# ElectroLab_R2.net
KiCad netlist of a schematic drawn in EAGLE
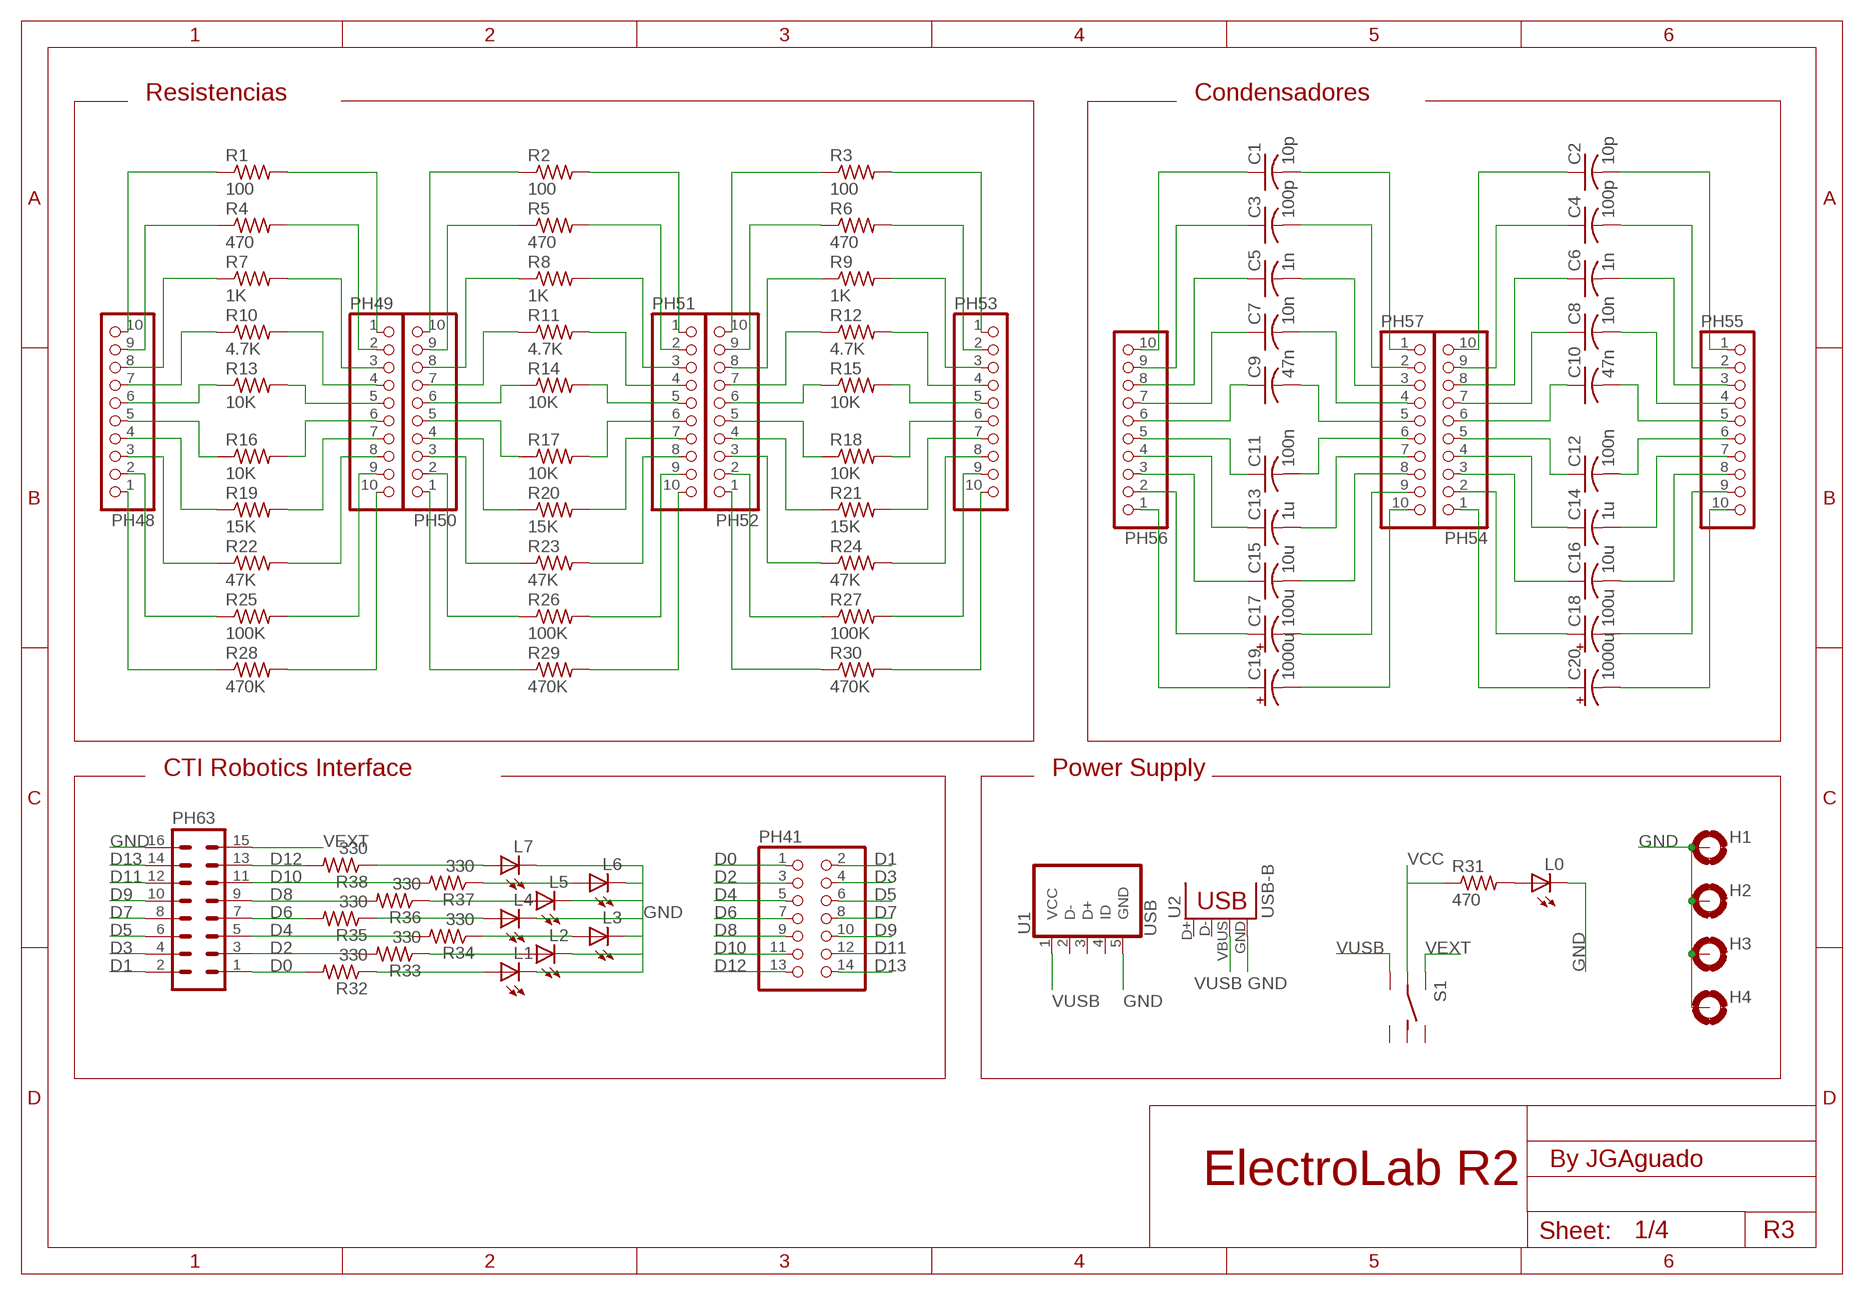
[diagram p0: schematic, sheet 1]
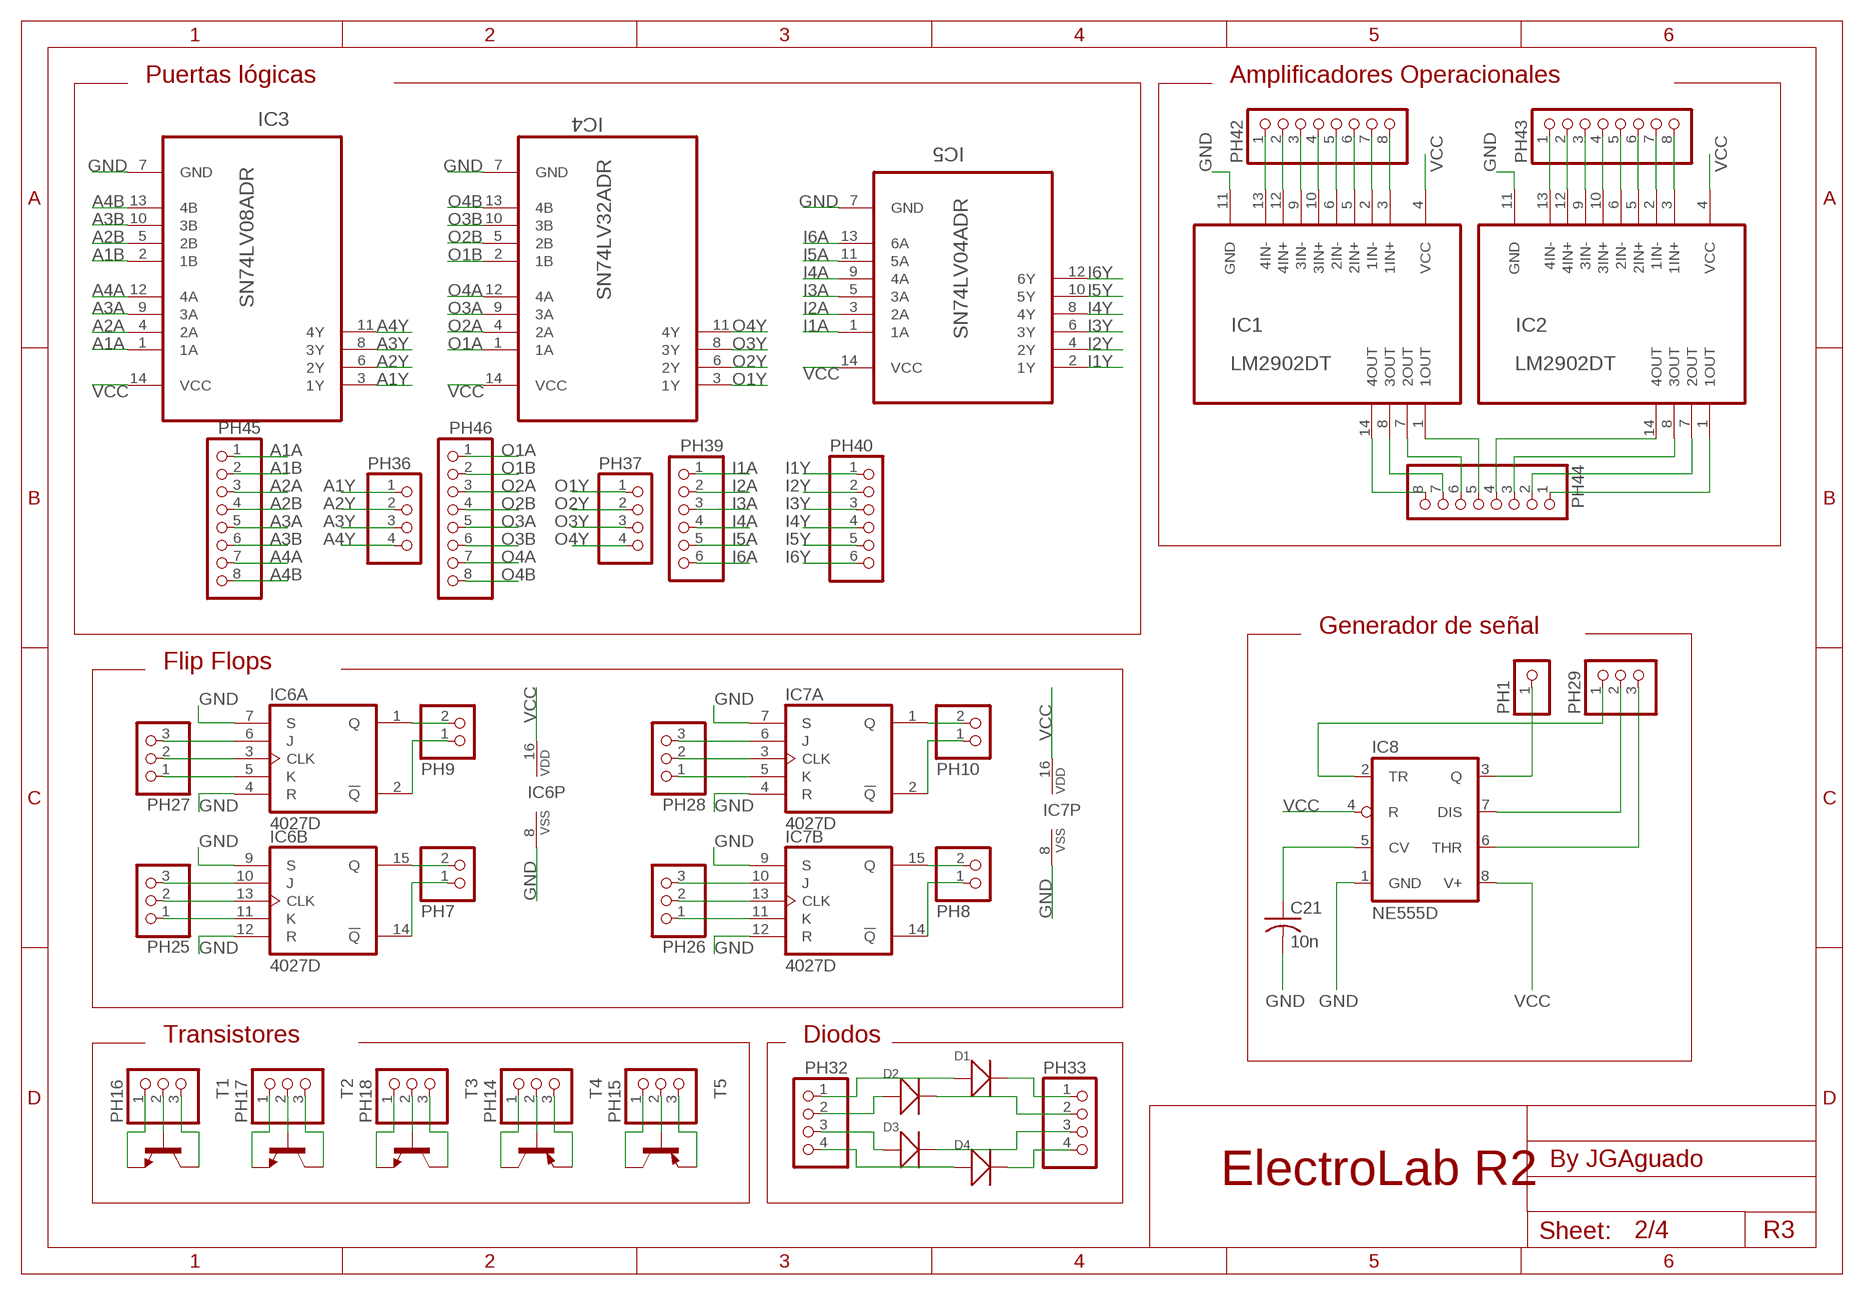
[diagram p1: schematic, sheet 2]
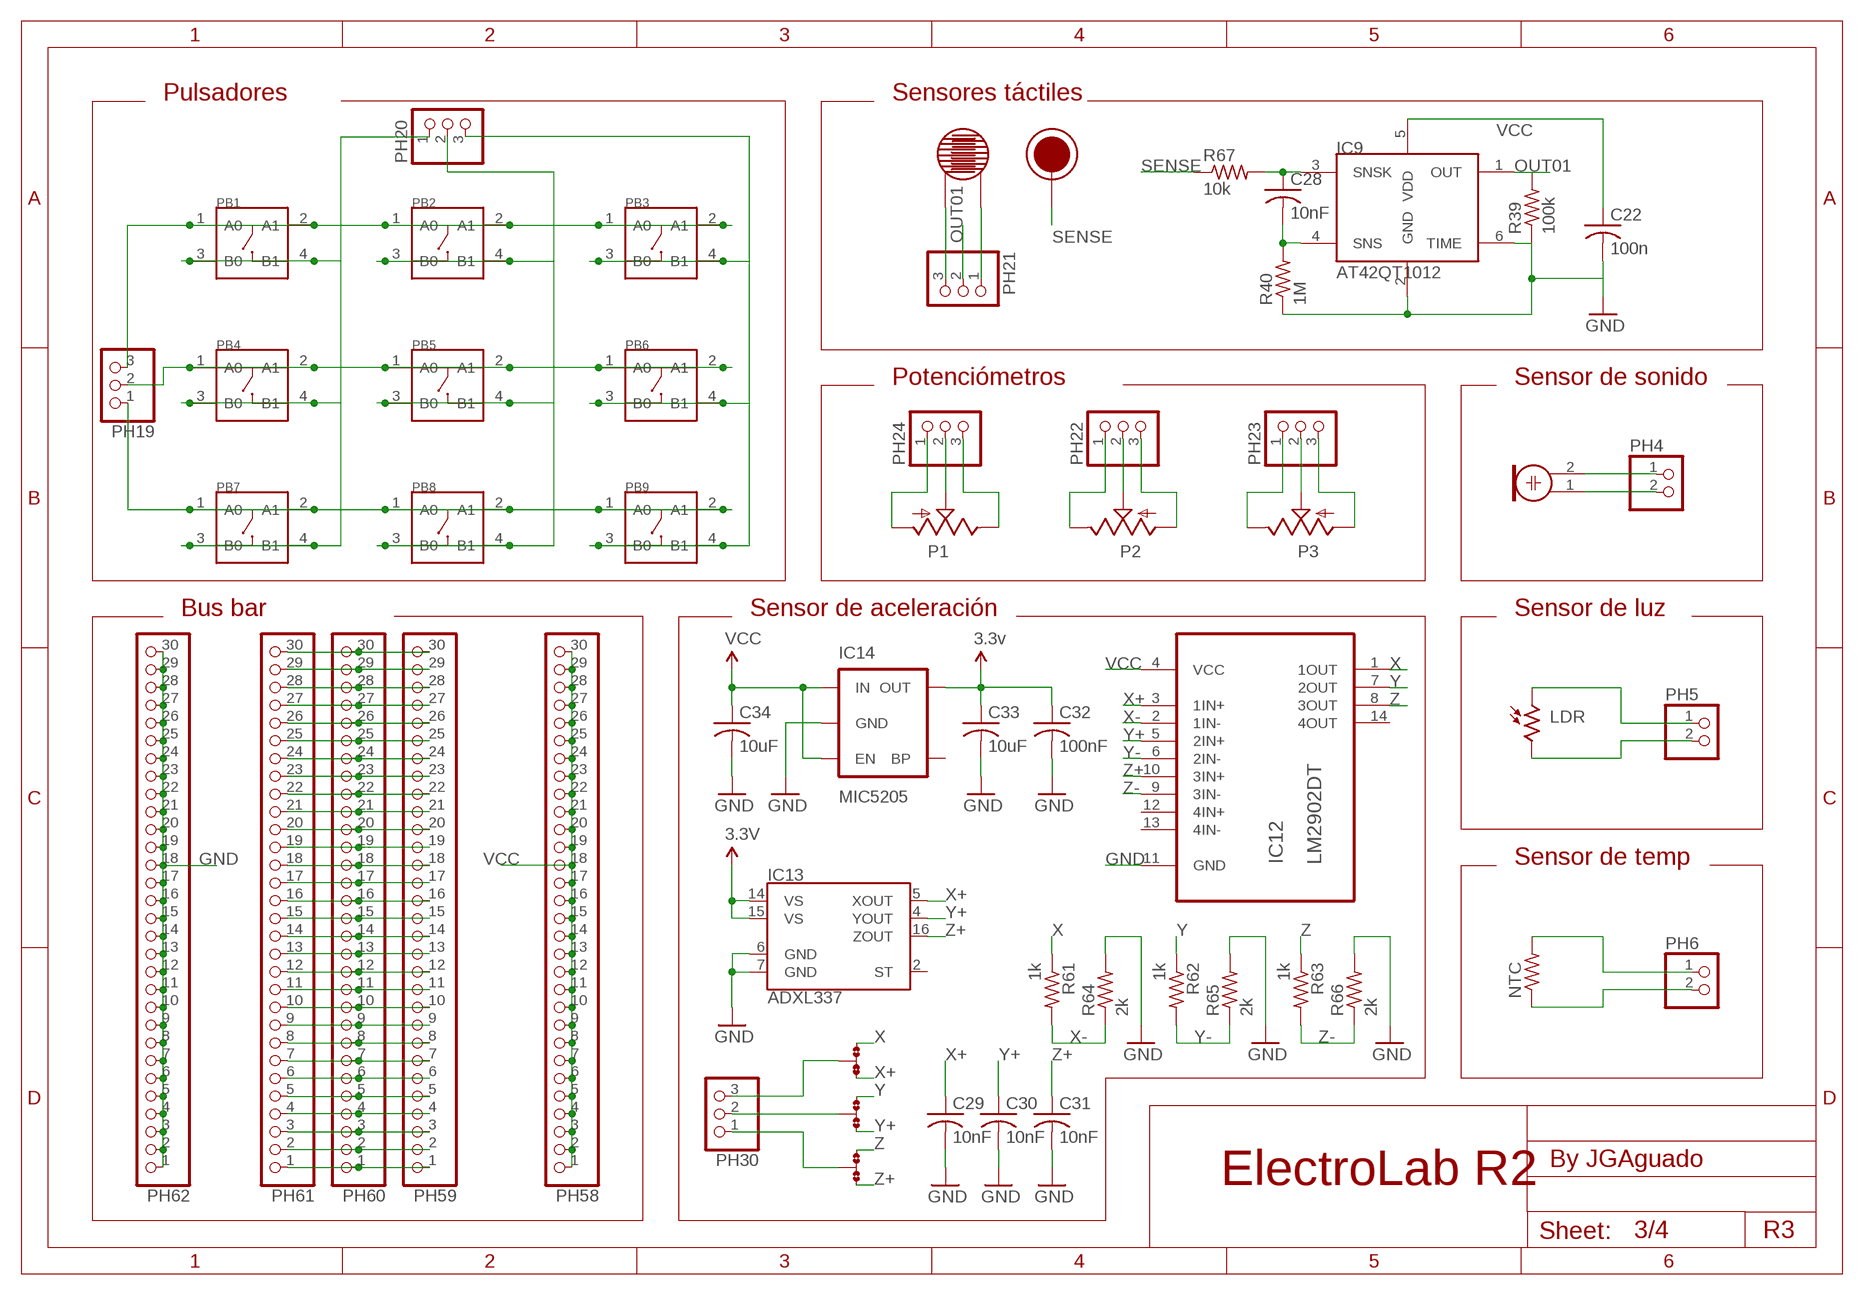
[diagram p2: schematic, sheet 3]
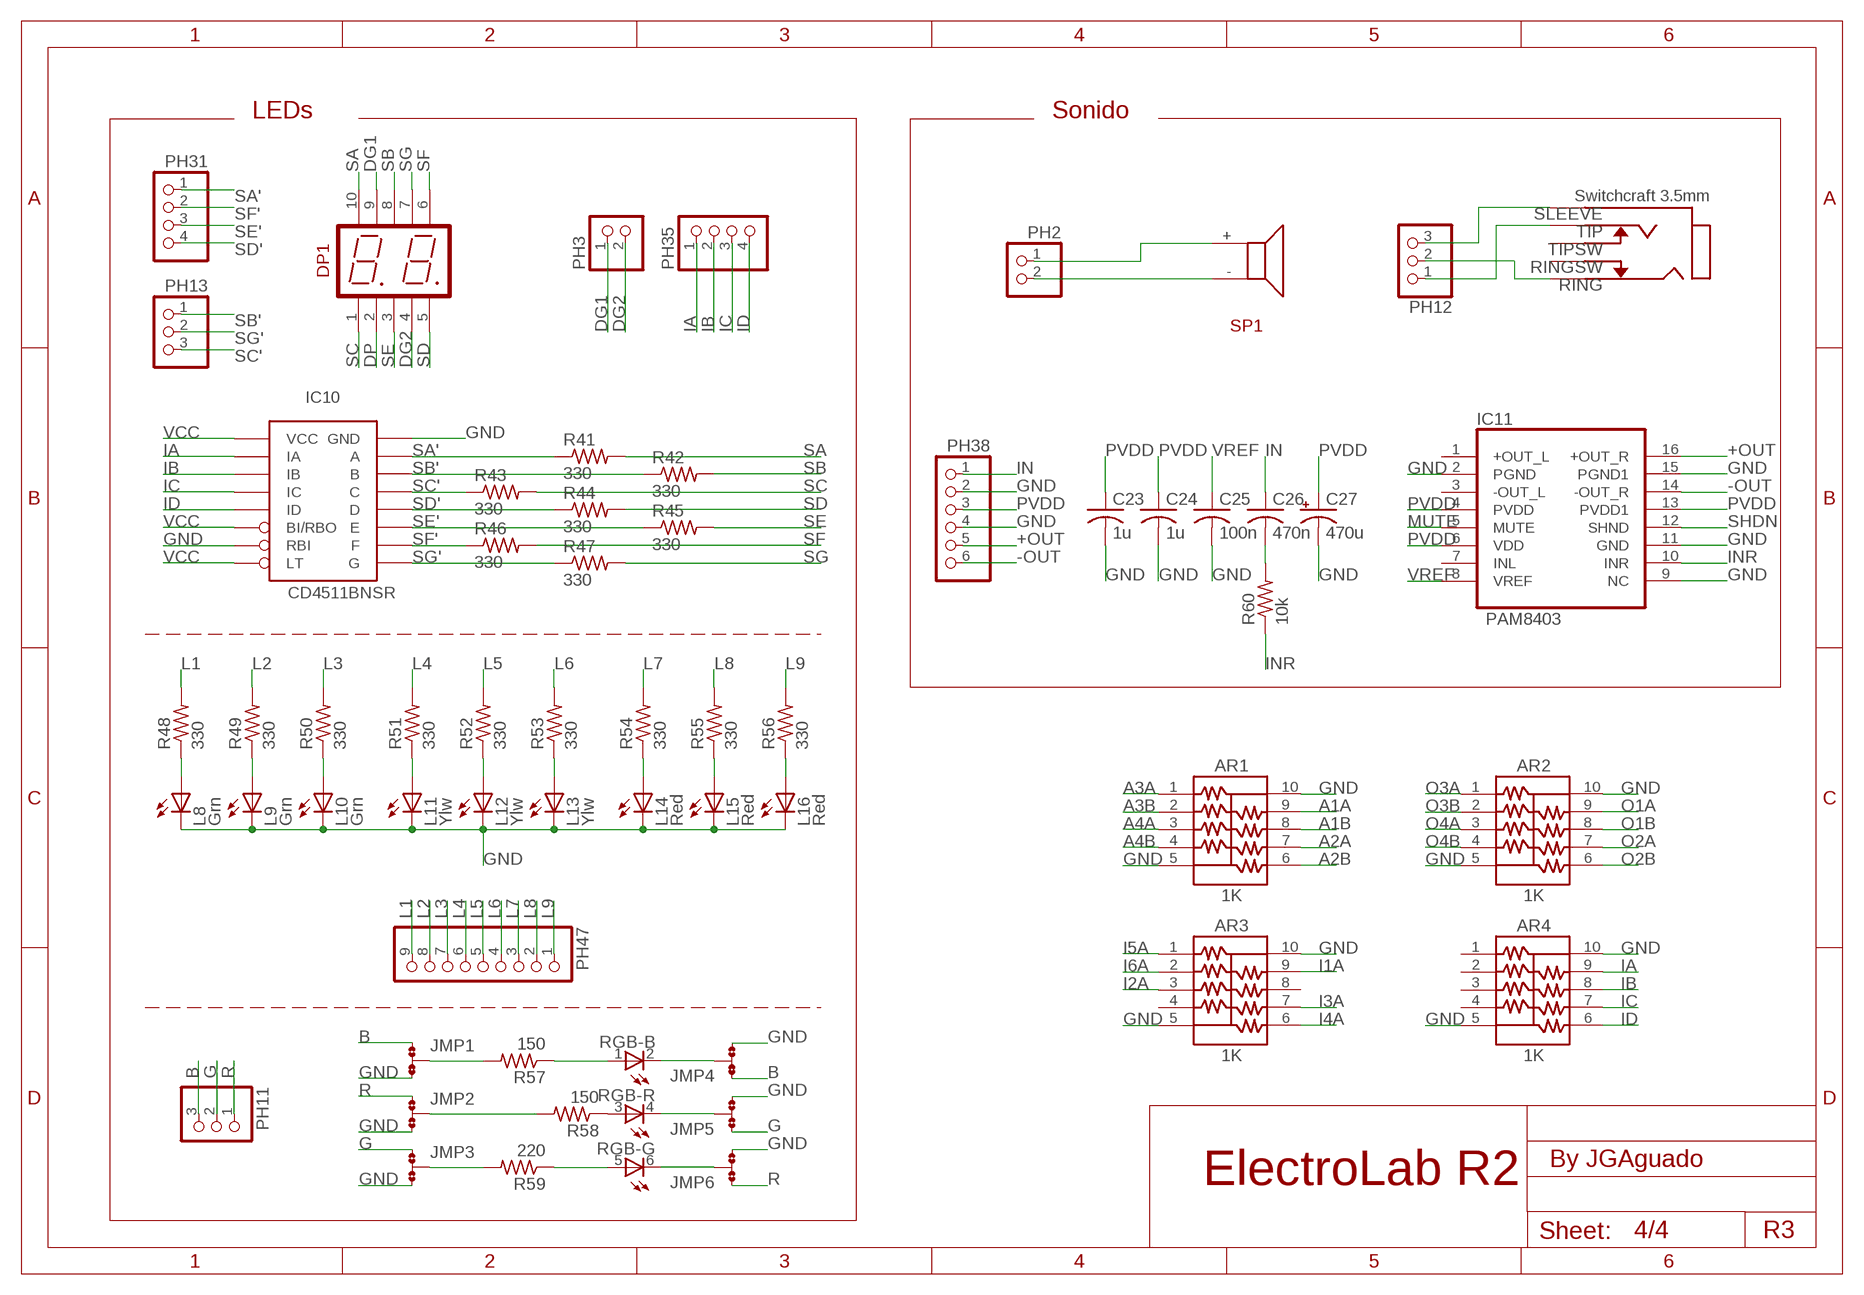
[diagram p3: schematic, sheet 4]

(export (version "E")
  (design (tool "Eeschema 10.0.6"))
  (components
    (comp (ref "C21")
      (value "10n")
      (footprint "eagle-import:C1206")
      (libsource (lib "eagle-import") (part "C-USC1206"))
    )
    (comp (ref "D1")
      (value "SMD-DIODE-SWITCHING-75V-150MA(D1206)")
      (footprint "eagle-import:LED-1206")
      (fields (field (name "MPN") "CD1206-S01575"))
      (libsource (lib "eagle-import") (part "SMD-DIODE-SWITCHING-75V-150MA(D1206)"))
    )
    (comp (ref "D2")
      (value "SMD-DIODE-SWITCHING-75V-150MA(D1206)")
      (footprint "eagle-import:LED-1206")
      (fields (field (name "MPN") "CD1206-S01575"))
      (libsource (lib "eagle-import") (part "SMD-DIODE-SWITCHING-75V-150MA(D1206)"))
    )
    (comp (ref "D3")
      (value "SMD-DIODE-SWITCHING-75V-150MA(D1206)")
      (footprint "eagle-import:LED-1206")
      (fields (field (name "MPN") "CD1206-S01575"))
      (libsource (lib "eagle-import") (part "SMD-DIODE-SWITCHING-75V-150MA(D1206)"))
    )
    (comp (ref "D4")
      (value "SMD-DIODE-SWITCHING-75V-150MA(D1206)")
      (footprint "eagle-import:LED-1206")
      (fields (field (name "MPN") "CD1206-S01575"))
      (libsource (lib "eagle-import") (part "SMD-DIODE-SWITCHING-75V-150MA(D1206)"))
    )
    (comp (ref "IC1")
      (value "LM2902DT")
      (footprint "eagle-import:SOIC127P600X175-14N")
      (libsource (lib "eagle-import") (part "LM2902DT"))
    )
    (comp (ref "IC2")
      (value "LM2902DT")
      (footprint "eagle-import:SOIC127P600X175-14N")
      (libsource (lib "eagle-import") (part "LM2902DT"))
    )
    (comp (ref "IC3")
      (value "SN74LV08ADR")
      (footprint "eagle-import:SOIC127P600X175-14N")
      (fields (field (name "MPN") "SN74LVC08AD"))
      (libsource (lib "eagle-import") (part "SN74LVC08AD"))
    )
    (comp (ref "IC4")
      (value "SN74LV32ADR")
      (footprint "eagle-import:SOIC127P600X175-14N")
      (fields (field (name "MPN") "SN74S32D"))
      (libsource (lib "eagle-import") (part "SN74S32D"))
    )
    (comp (ref "IC5")
      (value "SN74LV04ADR")
      (footprint "eagle-import:SOIC127P600X175-14N")
      (libsource (lib "eagle-import") (part "SN74LV04ADR"))
    )
    (comp (ref "IC6")
      (value "4027D")
      (footprint "eagle-import:SO16")
      (libsource (lib "eagle-import") (part "4027D"))
    )
    (comp (ref "IC7")
      (value "4027D")
      (footprint "eagle-import:SO16")
      (libsource (lib "eagle-import") (part "4027D"))
    )
    (comp (ref "IC8")
      (value "NE555D")
      (footprint "eagle-import:SO08")
      (libsource (lib "eagle-import") (part "555DNE"))
    )
    (comp (ref "PH1")
      (value "PINHD-1X1")
      (footprint "eagle-import:1X01")
      (libsource (lib "eagle-import") (part "PINHD-1X1"))
    )
    (comp (ref "PH7")
      (value "PINHD-1X2")
      (footprint "eagle-import:1X02")
      (libsource (lib "eagle-import") (part "PINHD-1X2"))
    )
    (comp (ref "PH8")
      (value "PINHD-1X2")
      (footprint "eagle-import:1X02")
      (libsource (lib "eagle-import") (part "PINHD-1X2"))
    )
    (comp (ref "PH9")
      (value "PINHD-1X2")
      (footprint "eagle-import:1X02")
      (libsource (lib "eagle-import") (part "PINHD-1X2"))
    )
    (comp (ref "PH10")
      (value "PINHD-1X2")
      (footprint "eagle-import:1X02")
      (libsource (lib "eagle-import") (part "PINHD-1X2"))
    )
    (comp (ref "PH14")
      (value "PINHD-1X3")
      (footprint "eagle-import:1X03")
      (libsource (lib "eagle-import") (part "PINHD-1X3"))
    )
    (comp (ref "PH15")
      (value "PINHD-1X3")
      (footprint "eagle-import:1X03")
      (libsource (lib "eagle-import") (part "PINHD-1X3"))
    )
    (comp (ref "PH16")
      (value "PINHD-1X3")
      (footprint "eagle-import:1X03")
      (libsource (lib "eagle-import") (part "PINHD-1X3"))
    )
    (comp (ref "PH17")
      (value "PINHD-1X3")
      (footprint "eagle-import:1X03")
      (libsource (lib "eagle-import") (part "PINHD-1X3"))
    )
    (comp (ref "PH18")
      (value "PINHD-1X3")
      (footprint "eagle-import:1X03")
      (libsource (lib "eagle-import") (part "PINHD-1X3"))
    )
    (comp (ref "PH25")
      (value "PINHD-1X3")
      (footprint "eagle-import:1X03")
      (libsource (lib "eagle-import") (part "PINHD-1X3"))
    )
    (comp (ref "PH26")
      (value "PINHD-1X3")
      (footprint "eagle-import:1X03")
      (libsource (lib "eagle-import") (part "PINHD-1X3"))
    )
    (comp (ref "PH27")
      (value "PINHD-1X3")
      (footprint "eagle-import:1X03")
      (libsource (lib "eagle-import") (part "PINHD-1X3"))
    )
    (comp (ref "PH28")
      (value "PINHD-1X3")
      (footprint "eagle-import:1X03")
      (libsource (lib "eagle-import") (part "PINHD-1X3"))
    )
    (comp (ref "PH29")
      (value "PINHD-1X3")
      (footprint "eagle-import:1X03")
      (libsource (lib "eagle-import") (part "PINHD-1X3"))
    )
    (comp (ref "PH32")
      (value "PINHD-1X4")
      (footprint "eagle-import:1X04")
      (libsource (lib "eagle-import") (part "PINHD-1X4"))
    )
    (comp (ref "PH33")
      (value "PINHD-1X4")
      (footprint "eagle-import:1X04")
      (libsource (lib "eagle-import") (part "PINHD-1X4"))
    )
    (comp (ref "PH36")
      (value "PINHD-1X4")
      (footprint "eagle-import:1X04")
      (libsource (lib "eagle-import") (part "PINHD-1X4"))
    )
    (comp (ref "PH37")
      (value "PINHD-1X4")
      (footprint "eagle-import:1X04")
      (libsource (lib "eagle-import") (part "PINHD-1X4"))
    )
    (comp (ref "PH39")
      (value "PINHD-1X6")
      (footprint "eagle-import:1X06")
      (libsource (lib "eagle-import") (part "PINHD-1X6"))
    )
    (comp (ref "PH40")
      (value "PINHD-1X6")
      (footprint "eagle-import:1X06")
      (libsource (lib "eagle-import") (part "PINHD-1X6"))
    )
    (comp (ref "PH42")
      (value "PINHD-1X8")
      (footprint "eagle-import:1X08")
      (libsource (lib "eagle-import") (part "PINHD-1X8"))
    )
    (comp (ref "PH43")
      (value "PINHD-1X8")
      (footprint "eagle-import:1X08")
      (libsource (lib "eagle-import") (part "PINHD-1X8"))
    )
    (comp (ref "PH44")
      (value "PINHD-1X8")
      (footprint "eagle-import:1X08")
      (libsource (lib "eagle-import") (part "PINHD-1X8"))
    )
    (comp (ref "PH45")
      (value "PINHD-1X8")
      (footprint "eagle-import:1X08")
      (libsource (lib "eagle-import") (part "PINHD-1X8"))
    )
    (comp (ref "PH46")
      (value "PINHD-1X8")
      (footprint "eagle-import:1X08")
      (libsource (lib "eagle-import") (part "PINHD-1X8"))
    )
    (comp (ref "T1")
      (value "BC817-16-NPN-SOT23-BEC")
      (footprint "eagle-import:SOT23-BEC")
      (libsource (lib "eagle-import") (part "-NPN-SOT23-BECBC817-16"))
    )
    (comp (ref "T2")
      (value "BC817-16-NPN-SOT23-BEC")
      (footprint "eagle-import:SOT23-BEC")
      (libsource (lib "eagle-import") (part "-NPN-SOT23-BECBC817-16"))
    )
    (comp (ref "T3")
      (value "BC817-16-NPN-SOT23-BEC")
      (footprint "eagle-import:SOT23-BEC")
      (libsource (lib "eagle-import") (part "-NPN-SOT23-BECBC817-16"))
    )
    (comp (ref "T4")
      (value "-PNP-SOT23-BCE")
      (footprint "eagle-import:SOT23-BCE")
      (libsource (lib "eagle-import") (part "-PNP-SOT23-BCE"))
    )
    (comp (ref "T5")
      (value "-PNP-SOT23-BCE")
      (footprint "eagle-import:SOT23-BCE")
      (libsource (lib "eagle-import") (part "-PNP-SOT23-BCE"))
    )
    (comp (ref "C22")
      (value "100n")
      (footprint "eagle-import:0603")
      (libsource (lib "eagle-import") (part "C0603"))
    )
    (comp (ref "C28")
      (value "10nF")
      (footprint "eagle-import:0603")
      (libsource (lib "eagle-import") (part "C0603"))
    )
    (comp (ref "C29")
      (value "10nF")
      (footprint "eagle-import:0603")
      (libsource (lib "eagle-import") (part "C0603"))
    )
    (comp (ref "C30")
      (value "10nF")
      (footprint "eagle-import:0603")
      (libsource (lib "eagle-import") (part "C0603"))
    )
    (comp (ref "C31")
      (value "10nF")
      (footprint "eagle-import:0603")
      (libsource (lib "eagle-import") (part "C0603"))
    )
    (comp (ref "C32")
      (value "100nF")
      (footprint "eagle-import:0603")
      (libsource (lib "eagle-import") (part "C0603"))
    )
    (comp (ref "C33")
      (value "10uF")
      (footprint "eagle-import:0603")
      (libsource (lib "eagle-import") (part "C0603"))
    )
    (comp (ref "C34")
      (value "10uF")
      (footprint "eagle-import:0603")
      (libsource (lib "eagle-import") (part "C0603"))
    )
    (comp (ref "IC9")
      (value "AT42QT1012")
      (footprint "eagle-import:SOT-23-6")
      (libsource (lib "eagle-import") (part "AT42QT1012"))
    )
    (comp (ref "IC12")
      (value "LM2902DT")
      (footprint "eagle-import:SOIC127P600X175-14N")
      (libsource (lib "eagle-import") (part "LM2902DT"))
    )
    (comp (ref "IC13")
      (value "ADXL337")
      (footprint "eagle-import:LFCSP-3X3")
      (libsource (lib "eagle-import") (part "ADXL337"))
    )
    (comp (ref "IC14")
      (value "MIC5205")
      (footprint "eagle-import:SOT23-5")
      (libsource (lib "eagle-import") (part "V_REG_LDOSMD"))
    )
    (comp (ref "JMP7")
      (value "0R-JUMPA")
      (footprint "eagle-import:A0R-JMP")
      (libsource (lib "eagle-import") (part "jump-0r-smd_251_0R-JUMPA"))
    )
    (comp (ref "JMP8")
      (value "0R-JUMPA")
      (footprint "eagle-import:A0R-JMP")
      (libsource (lib "eagle-import") (part "jump-0r-smd_251_0R-JUMPA"))
    )
    (comp (ref "JMP9")
      (value "0R-JUMPA")
      (footprint "eagle-import:A0R-JMP")
      (libsource (lib "eagle-import") (part "jump-0r-smd_251_0R-JUMPA"))
    )
    (comp (ref "LDR")
      (value "V1060_21")
      (footprint "eagle-import:TO-5_V10")
      (libsource (lib "eagle-import") (part "?1060V_21"))
    )
    (comp (ref "MIC")
      (value "ELECTRET_MICROPHON-WM-64PC/64PK")
      (footprint "eagle-import:WM-64PC_64PK")
      (libsource (lib "eagle-import") (part "ELECTRET_MICROPHON-WM-64PC/64PK"))
    )
    (comp (ref "NTC")
      (value "R-US_R1206")
      (footprint "eagle-import:R1206")
      (libsource (lib "eagle-import") (part "R-US_R1206"))
    )
    (comp (ref "P1")
      (value "SLIDE_POT_20MM")
      (footprint "eagle-import:SLIDE_POT_20MM")
      (libsource (lib "eagle-import") (part "SLIDE_POT_20MM"))
    )
    (comp (ref "P2")
      (value "ALPS_RK09K_VERTICAL")
      (footprint "eagle-import:ALPS_RK09K_VERTICAL")
      (libsource (lib "eagle-import") (part "ALPS_RK09K_VERTICAL"))
    )
    (comp (ref "P3")
      (value "ALPS_RK09K_VERTICAL")
      (footprint "eagle-import:ALPS_RK09K_VERTICAL")
      (libsource (lib "eagle-import") (part "ALPS_RK09K_VERTICAL"))
    )
    (comp (ref "PB1")
      (value "SMD-SWITCH-TACTILE-SPST-NO/TS-1109(4P-D6.0MM)")
      (footprint "eagle-import:SW4-SMD-6.0X6.0X5.0MM")
      (fields (field (name "MPN") "TS-1109"))
      (libsource (lib "eagle-import") (part "SMD-SWITCH-TACTILE-SPST-NO/TS-1109(4P-D6.0MM)"))
    )
    (comp (ref "PB2")
      (value "SMD-SWITCH-TACTILE-SPST-NO/TS-1109(4P-D6.0MM)")
      (footprint "eagle-import:SW4-SMD-6.0X6.0X5.0MM")
      (fields (field (name "MPN") "TS-1109"))
      (libsource (lib "eagle-import") (part "SMD-SWITCH-TACTILE-SPST-NO/TS-1109(4P-D6.0MM)"))
    )
    (comp (ref "PB3")
      (value "SMD-SWITCH-TACTILE-SPST-NO/TS-1109(4P-D6.0MM)")
      (footprint "eagle-import:SW4-SMD-6.0X6.0X5.0MM")
      (fields (field (name "MPN") "TS-1109"))
      (libsource (lib "eagle-import") (part "SMD-SWITCH-TACTILE-SPST-NO/TS-1109(4P-D6.0MM)"))
    )
    (comp (ref "PB4")
      (value "SMD-SWITCH-TACTILE-SPST-NO/TS-1109(4P-D6.0MM)")
      (footprint "eagle-import:SW4-SMD-6.0X6.0X5.0MM")
      (fields (field (name "MPN") "TS-1109"))
      (libsource (lib "eagle-import") (part "SMD-SWITCH-TACTILE-SPST-NO/TS-1109(4P-D6.0MM)"))
    )
    (comp (ref "PB5")
      (value "SMD-SWITCH-TACTILE-SPST-NO/TS-1109(4P-D6.0MM)")
      (footprint "eagle-import:SW4-SMD-6.0X6.0X5.0MM")
      (fields (field (name "MPN") "TS-1109"))
      (libsource (lib "eagle-import") (part "SMD-SWITCH-TACTILE-SPST-NO/TS-1109(4P-D6.0MM)"))
    )
    (comp (ref "PB6")
      (value "SMD-SWITCH-TACTILE-SPST-NO/TS-1109(4P-D6.0MM)")
      (footprint "eagle-import:SW4-SMD-6.0X6.0X5.0MM")
      (fields (field (name "MPN") "TS-1109"))
      (libsource (lib "eagle-import") (part "SMD-SWITCH-TACTILE-SPST-NO/TS-1109(4P-D6.0MM)"))
    )
    (comp (ref "PB7")
      (value "SMD-SWITCH-TACTILE-SPST-NO/TS-1109(4P-D6.0MM)")
      (footprint "eagle-import:SW4-SMD-6.0X6.0X5.0MM")
      (fields (field (name "MPN") "TS-1109"))
      (libsource (lib "eagle-import") (part "SMD-SWITCH-TACTILE-SPST-NO/TS-1109(4P-D6.0MM)"))
    )
    (comp (ref "PB8")
      (value "SMD-SWITCH-TACTILE-SPST-NO/TS-1109(4P-D6.0MM)")
      (footprint "eagle-import:SW4-SMD-6.0X6.0X5.0MM")
      (fields (field (name "MPN") "TS-1109"))
      (libsource (lib "eagle-import") (part "SMD-SWITCH-TACTILE-SPST-NO/TS-1109(4P-D6.0MM)"))
    )
    (comp (ref "PB9")
      (value "SMD-SWITCH-TACTILE-SPST-NO/TS-1109(4P-D6.0MM)")
      (footprint "eagle-import:SW4-SMD-6.0X6.0X5.0MM")
      (fields (field (name "MPN") "TS-1109"))
      (libsource (lib "eagle-import") (part "SMD-SWITCH-TACTILE-SPST-NO/TS-1109(4P-D6.0MM)"))
    )
    (comp (ref "PH4")
      (value "PINHD-1X2")
      (footprint "eagle-import:1X02")
      (libsource (lib "eagle-import") (part "PINHD-1X2"))
    )
    (comp (ref "PH5")
      (value "PINHD-1X2")
      (footprint "eagle-import:1X02")
      (libsource (lib "eagle-import") (part "PINHD-1X2"))
    )
    (comp (ref "PH6")
      (value "PINHD-1X2")
      (footprint "eagle-import:1X02")
      (libsource (lib "eagle-import") (part "PINHD-1X2"))
    )
    (comp (ref "PH19")
      (value "PINHD-1X3")
      (footprint "eagle-import:1X03")
      (libsource (lib "eagle-import") (part "PINHD-1X3"))
    )
    (comp (ref "PH20")
      (value "PINHD-1X3")
      (footprint "eagle-import:1X03")
      (libsource (lib "eagle-import") (part "PINHD-1X3"))
    )
    (comp (ref "PH21")
      (value "PINHD-1X3")
      (footprint "eagle-import:1X03")
      (libsource (lib "eagle-import") (part "PINHD-1X3"))
    )
    (comp (ref "PH22")
      (value "PINHD-1X3")
      (footprint "eagle-import:1X03")
      (libsource (lib "eagle-import") (part "PINHD-1X3"))
    )
    (comp (ref "PH23")
      (value "PINHD-1X3")
      (footprint "eagle-import:1X03")
      (libsource (lib "eagle-import") (part "PINHD-1X3"))
    )
    (comp (ref "PH24")
      (value "PINHD-1X3")
      (footprint "eagle-import:1X03")
      (libsource (lib "eagle-import") (part "PINHD-1X3"))
    )
    (comp (ref "PH30")
      (value "PINHD-1X3")
      (footprint "eagle-import:1X03")
      (libsource (lib "eagle-import") (part "PINHD-1X3"))
    )
    (comp (ref "PH58")
      (value "PINHD-1X30")
      (footprint "eagle-import:1X30")
      (libsource (lib "eagle-import") (part "PINHD-1X30"))
    )
    (comp (ref "PH59")
      (value "PINHD-1X30")
      (footprint "eagle-import:1X30")
      (libsource (lib "eagle-import") (part "PINHD-1X30"))
    )
    (comp (ref "PH60")
      (value "PINHD-1X30")
      (footprint "eagle-import:1X30")
      (libsource (lib "eagle-import") (part "PINHD-1X30"))
    )
    (comp (ref "PH61")
      (value "PINHD-1X30")
      (footprint "eagle-import:1X30")
      (libsource (lib "eagle-import") (part "PINHD-1X30"))
    )
    (comp (ref "PH62")
      (value "PINHD-1X30")
      (footprint "eagle-import:1X30")
      (libsource (lib "eagle-import") (part "PINHD-1X30"))
    )
    (comp (ref "R39")
      (value "100k")
      (footprint "eagle-import:0603")
      (libsource (lib "eagle-import") (part "R0603"))
    )
    (comp (ref "R40")
      (value "1M")
      (footprint "eagle-import:0603")
      (libsource (lib "eagle-import") (part "R0603"))
    )
    (comp (ref "R61")
      (value "1k")
      (footprint "eagle-import:0603")
      (libsource (lib "eagle-import") (part "R0603"))
    )
    (comp (ref "R62")
      (value "1k")
      (footprint "eagle-import:0603")
      (libsource (lib "eagle-import") (part "R0603"))
    )
    (comp (ref "R63")
      (value "1k")
      (footprint "eagle-import:0603")
      (libsource (lib "eagle-import") (part "R0603"))
    )
    (comp (ref "R64")
      (value "2k")
      (footprint "eagle-import:0603")
      (libsource (lib "eagle-import") (part "R0603"))
    )
    (comp (ref "R65")
      (value "2k")
      (footprint "eagle-import:0603")
      (libsource (lib "eagle-import") (part "R0603"))
    )
    (comp (ref "R66")
      (value "2k")
      (footprint "eagle-import:0603")
      (libsource (lib "eagle-import") (part "R0603"))
    )
    (comp (ref "R67")
      (value "10k")
      (footprint "eagle-import:0603")
      (libsource (lib "eagle-import") (part "R0603"))
    )
    (comp (ref "U$15")
      (value "CAPACITIVE_SENSOR_PAD")
      (footprint "eagle-import:CAPACITIVE_SENSOR_PAD")
      (libsource (lib "eagle-import") (part "CAPACITIVE_SENSOR_PAD"))
    )
    (comp (ref "U$16")
      (value "RESISTIVE_SENSOR_PAD")
      (footprint "eagle-import:RESISTIVE_SENSOR_PAD")
      (libsource (lib "eagle-import") (part "RESISTIVE_SENSOR_PAD"))
    )
    (comp (ref "AR1")
      (value "1K")
      (footprint "eagle-import:RESISTOR_ARRAY_X8_CAY17")
      (libsource (lib "eagle-import") (part "RESISTOR_ARRAY_X8_CAY17"))
    )
    (comp (ref "AR2")
      (value "1K")
      (footprint "eagle-import:RESISTOR_ARRAY_X8_CAY17")
      (libsource (lib "eagle-import") (part "RESISTOR_ARRAY_X8_CAY17"))
    )
    (comp (ref "AR3")
      (value "1K")
      (footprint "eagle-import:RESISTOR_ARRAY_X8_CAY17")
      (libsource (lib "eagle-import") (part "RESISTOR_ARRAY_X8_CAY17"))
    )
    (comp (ref "AR4")
      (value "1K")
      (footprint "eagle-import:RESISTOR_ARRAY_X8_CAY17")
      (libsource (lib "eagle-import") (part "RESISTOR_ARRAY_X8_CAY17"))
    )
    (comp (ref "C23")
      (value "1u")
      (footprint "eagle-import:C1206")
      (libsource (lib "eagle-import") (part "C-USC1206"))
    )
    (comp (ref "C24")
      (value "1u")
      (footprint "eagle-import:C1206")
      (libsource (lib "eagle-import") (part "C-USC1206"))
    )
    (comp (ref "C25")
      (value "100n")
      (footprint "eagle-import:C1206")
      (libsource (lib "eagle-import") (part "C-USC1206"))
    )
    (comp (ref "C26")
      (value "470n")
      (footprint "eagle-import:C1206")
      (libsource (lib "eagle-import") (part "C-USC1206"))
    )
    (comp (ref "C27")
      (value "470u")
      (footprint "eagle-import:D_7343-31W")
      (libsource (lib "eagle-import") (part "CPOL-USD/7343-31W"))
    )
    (comp (ref "DP1")
      (value "2X7_SEGMENT_COMMON_CATODE_12_PINS")
      (footprint "eagle-import:2X7_SEGMENT_COMMON_CATODE_12_PINS")
      (libsource (lib "eagle-import") (part "2X7_SEGMENT_COMMON_CATODE_12_PINS"))
    )
    (comp (ref "IC10")
      (value "CD4511BNSR")
      (footprint "eagle-import:SN74LS247D")
      (libsource (lib "eagle-import") (part "SN74LS247D"))
    )
    (comp (ref "IC11")
      (value "PAM8403")
      (footprint "eagle-import:SOP-16")
      (libsource (lib "eagle-import") (part "PAM8403"))
    )
    (comp (ref "JC1")
      (value "SWTCHCRFT_3.5JACK5-JACK-SMD")
      (footprint "eagle-import:4-JACK-SMD")
      (libsource (lib "eagle-import") (part "SWTCHCRFT_3.5JACK5-JACK-SMD"))
    )
    (comp (ref "JMP1")
      (value "0R-JUMPA")
      (footprint "eagle-import:A0R-JMP")
      (libsource (lib "eagle-import") (part "0R-JUMPA"))
    )
    (comp (ref "JMP2")
      (value "0R-JUMPA")
      (footprint "eagle-import:A0R-JMP")
      (libsource (lib "eagle-import") (part "0R-JUMPA"))
    )
    (comp (ref "JMP3")
      (value "0R-JUMPA")
      (footprint "eagle-import:A0R-JMP")
      (libsource (lib "eagle-import") (part "0R-JUMPA"))
    )
    (comp (ref "JMP4")
      (value "0R-JUMPA")
      (footprint "eagle-import:A0R-JMP")
      (libsource (lib "eagle-import") (part "0R-JUMPA"))
    )
    (comp (ref "JMP5")
      (value "0R-JUMPA")
      (footprint "eagle-import:A0R-JMP")
      (libsource (lib "eagle-import") (part "0R-JUMPA"))
    )
    (comp (ref "JMP6")
      (value "0R-JUMPA")
      (footprint "eagle-import:A0R-JMP")
      (libsource (lib "eagle-import") (part "0R-JUMPA"))
    )
    (comp (ref "L8")
      (value "Grn")
      (footprint "eagle-import:1206")
      (libsource (lib "eagle-import") (part "LEDSMT1206"))
    )
    (comp (ref "L9")
      (value "Grn")
      (footprint "eagle-import:1206")
      (libsource (lib "eagle-import") (part "LEDSMT1206"))
    )
    (comp (ref "L10")
      (value "Grn")
      (footprint "eagle-import:1206")
      (libsource (lib "eagle-import") (part "LEDSMT1206"))
    )
    (comp (ref "L11")
      (value "Ylw")
      (footprint "eagle-import:1206")
      (libsource (lib "eagle-import") (part "LEDSMT1206"))
    )
    (comp (ref "L12")
      (value "Ylw")
      (footprint "eagle-import:1206")
      (libsource (lib "eagle-import") (part "LEDSMT1206"))
    )
    (comp (ref "L13")
      (value "Ylw")
      (footprint "eagle-import:1206")
      (libsource (lib "eagle-import") (part "LEDSMT1206"))
    )
    (comp (ref "L14")
      (value "Red")
      (footprint "eagle-import:1206")
      (libsource (lib "eagle-import") (part "LEDSMT1206"))
    )
    (comp (ref "L15")
      (value "Red")
      (footprint "eagle-import:1206")
      (libsource (lib "eagle-import") (part "LEDSMT1206"))
    )
    (comp (ref "L16")
      (value "Red")
      (footprint "eagle-import:1206")
      (libsource (lib "eagle-import") (part "LEDSMT1206"))
    )
    (comp (ref "PH2")
      (value "PINHD-1X2")
      (footprint "eagle-import:1X02")
      (libsource (lib "eagle-import") (part "PINHD-1X2"))
    )
    (comp (ref "PH3")
      (value "PINHD-1X2")
      (footprint "eagle-import:1X02")
      (libsource (lib "eagle-import") (part "PINHD-1X2"))
    )
    (comp (ref "PH11")
      (value "PINHD-1X3")
      (footprint "eagle-import:1X03")
      (libsource (lib "eagle-import") (part "PINHD-1X3"))
    )
    (comp (ref "PH12")
      (value "PINHD-1X3")
      (footprint "eagle-import:1X03")
      (libsource (lib "eagle-import") (part "PINHD-1X3"))
    )
    (comp (ref "PH13")
      (value "PINHD-1X3")
      (footprint "eagle-import:1X03")
      (libsource (lib "eagle-import") (part "PINHD-1X3"))
    )
    (comp (ref "PH31")
      (value "PINHD-1X4")
      (footprint "eagle-import:1X04")
      (libsource (lib "eagle-import") (part "PINHD-1X4"))
    )
    (comp (ref "PH35")
      (value "PINHD-1X4")
      (footprint "eagle-import:1X04")
      (libsource (lib "eagle-import") (part "PINHD-1X4"))
    )
    (comp (ref "PH38")
      (value "PINHD-1X6")
      (footprint "eagle-import:1X06")
      (libsource (lib "eagle-import") (part "PINHD-1X6"))
    )
    (comp (ref "PH47")
      (value "PINHD-1X9")
      (footprint "eagle-import:1X09")
      (libsource (lib "eagle-import") (part "PINHD-1X9"))
    )
    (comp (ref "R41")
      (value "330")
      (footprint "eagle-import:R1206")
      (libsource (lib "eagle-import") (part "resistor_R-US_R1206"))
    )
    (comp (ref "R42")
      (value "330")
      (footprint "eagle-import:R1206")
      (libsource (lib "eagle-import") (part "resistor_R-US_R1206"))
    )
    (comp (ref "R43")
      (value "330")
      (footprint "eagle-import:R1206")
      (libsource (lib "eagle-import") (part "resistor_R-US_R1206"))
    )
    (comp (ref "R44")
      (value "330")
      (footprint "eagle-import:R1206")
      (libsource (lib "eagle-import") (part "resistor_R-US_R1206"))
    )
    (comp (ref "R45")
      (value "330")
      (footprint "eagle-import:R1206")
      (libsource (lib "eagle-import") (part "resistor_R-US_R1206"))
    )
    (comp (ref "R46")
      (value "330")
      (footprint "eagle-import:R1206")
      (libsource (lib "eagle-import") (part "resistor_R-US_R1206"))
    )
    (comp (ref "R47")
      (value "330")
      (footprint "eagle-import:R1206")
      (libsource (lib "eagle-import") (part "resistor_R-US_R1206"))
    )
    (comp (ref "R48")
      (value "330")
      (footprint "eagle-import:R1206")
      (libsource (lib "eagle-import") (part "resistor_R-US_R1206"))
    )
    (comp (ref "R49")
      (value "330")
      (footprint "eagle-import:R1206")
      (libsource (lib "eagle-import") (part "resistor_R-US_R1206"))
    )
    (comp (ref "R50")
      (value "330")
      (footprint "eagle-import:R1206")
      (libsource (lib "eagle-import") (part "resistor_R-US_R1206"))
    )
    (comp (ref "R51")
      (value "330")
      (footprint "eagle-import:R1206")
      (libsource (lib "eagle-import") (part "resistor_R-US_R1206"))
    )
    (comp (ref "R52")
      (value "330")
      (footprint "eagle-import:R1206")
      (libsource (lib "eagle-import") (part "resistor_R-US_R1206"))
    )
    (comp (ref "R53")
      (value "330")
      (footprint "eagle-import:R1206")
      (libsource (lib "eagle-import") (part "resistor_R-US_R1206"))
    )
    (comp (ref "R54")
      (value "330")
      (footprint "eagle-import:R1206")
      (libsource (lib "eagle-import") (part "resistor_R-US_R1206"))
    )
    (comp (ref "R55")
      (value "330")
      (footprint "eagle-import:R1206")
      (libsource (lib "eagle-import") (part "resistor_R-US_R1206"))
    )
    (comp (ref "R56")
      (value "330")
      (footprint "eagle-import:R1206")
      (libsource (lib "eagle-import") (part "resistor_R-US_R1206"))
    )
    (comp (ref "R57")
      (value "150")
      (footprint "eagle-import:R1206")
      (libsource (lib "eagle-import") (part "resistor_R-US_R1206"))
    )
    (comp (ref "R58")
      (value "150")
      (footprint "eagle-import:R1206")
      (libsource (lib "eagle-import") (part "resistor_R-US_R1206"))
    )
    (comp (ref "R59")
      (value "220")
      (footprint "eagle-import:R1206")
      (libsource (lib "eagle-import") (part "resistor_R-US_R1206"))
    )
    (comp (ref "R60")
      (value "10k")
      (footprint "eagle-import:R1206")
      (libsource (lib "eagle-import") (part "resistor_R-US_R1206"))
    )
    (comp (ref "RGB")
      (value "OVSTRGBBCR8")
      (footprint "eagle-import:OVSTRGBBCR8")
      (libsource (lib "eagle-import") (part "OVSTRGBBCR8"))
    )
    (comp (ref "SP1")
      (value "32MM_SPEAKER")
      (footprint "eagle-import:32MM_SPEAKER")
      (libsource (lib "eagle-import") (part "32MM_SPEAKER"))
    )
    (comp (ref "C1")
      (value "10p")
      (footprint "eagle-import:C1206")
      (libsource (lib "eagle-import") (part "C-USC1206"))
    )
    (comp (ref "C2")
      (value "10p")
      (footprint "eagle-import:C1206")
      (libsource (lib "eagle-import") (part "C-USC1206"))
    )
    (comp (ref "C3")
      (value "100p")
      (footprint "eagle-import:C1206")
      (libsource (lib "eagle-import") (part "C-USC1206"))
    )
    (comp (ref "C4")
      (value "100p")
      (footprint "eagle-import:C1206")
      (libsource (lib "eagle-import") (part "C-USC1206"))
    )
    (comp (ref "C5")
      (value "1n")
      (footprint "eagle-import:C1206")
      (libsource (lib "eagle-import") (part "C-USC1206"))
    )
    (comp (ref "C6")
      (value "1n")
      (footprint "eagle-import:C1206")
      (libsource (lib "eagle-import") (part "C-USC1206"))
    )
    (comp (ref "C7")
      (value "10n")
      (footprint "eagle-import:C1206")
      (libsource (lib "eagle-import") (part "C-USC1206"))
    )
    (comp (ref "C8")
      (value "10n")
      (footprint "eagle-import:C1206")
      (libsource (lib "eagle-import") (part "C-USC1206"))
    )
    (comp (ref "C9")
      (value "47n")
      (footprint "eagle-import:C1206")
      (libsource (lib "eagle-import") (part "C-USC1206"))
    )
    (comp (ref "C10")
      (value "47n")
      (footprint "eagle-import:C1206")
      (libsource (lib "eagle-import") (part "C-USC1206"))
    )
    (comp (ref "C11")
      (value "100n")
      (footprint "eagle-import:C1206")
      (libsource (lib "eagle-import") (part "C-USC1206"))
    )
    (comp (ref "C12")
      (value "100n")
      (footprint "eagle-import:C1206")
      (libsource (lib "eagle-import") (part "C-USC1206"))
    )
    (comp (ref "C13")
      (value "1u")
      (footprint "eagle-import:C1206")
      (libsource (lib "eagle-import") (part "C-USC1206"))
    )
    (comp (ref "C14")
      (value "1u")
      (footprint "eagle-import:C1206")
      (libsource (lib "eagle-import") (part "C-USC1206"))
    )
    (comp (ref "C15")
      (value "10u")
      (footprint "eagle-import:C1206")
      (libsource (lib "eagle-import") (part "C-USC1206"))
    )
    (comp (ref "C16")
      (value "10u")
      (footprint "eagle-import:C1206")
      (libsource (lib "eagle-import") (part "C-USC1206"))
    )
    (comp (ref "C17")
      (value "100u")
      (footprint "eagle-import:A_3216-18W")
      (libsource (lib "eagle-import") (part "CPOL-USA/3216-18W"))
    )
    (comp (ref "C18")
      (value "100u")
      (footprint "eagle-import:A_3216-18W")
      (libsource (lib "eagle-import") (part "CPOL-USA/3216-18W"))
    )
    (comp (ref "C19")
      (value "1000u")
      (footprint "eagle-import:D_7343-31W")
      (libsource (lib "eagle-import") (part "CPOL-USD/7343-31W"))
    )
    (comp (ref "C20")
      (value "1000u")
      (footprint "eagle-import:D_7343-31W")
      (libsource (lib "eagle-import") (part "CPOL-USD/7343-31W"))
    )
    (comp (ref "H1")
      (value "MOUNT-PAD-ROUND2.8")
      (footprint "eagle-import:2,8-PAD")
      (libsource (lib "eagle-import") (part "MOUNT-PAD-ROUND2.8"))
    )
    (comp (ref "H2")
      (value "MOUNT-PAD-ROUND2.8")
      (footprint "eagle-import:2,8-PAD")
      (libsource (lib "eagle-import") (part "MOUNT-PAD-ROUND2.8"))
    )
    (comp (ref "H3")
      (value "MOUNT-PAD-ROUND2.8")
      (footprint "eagle-import:2,8-PAD")
      (libsource (lib "eagle-import") (part "MOUNT-PAD-ROUND2.8"))
    )
    (comp (ref "H4")
      (value "MOUNT-PAD-ROUND2.8")
      (footprint "eagle-import:2,8-PAD")
      (libsource (lib "eagle-import") (part "MOUNT-PAD-ROUND2.8"))
    )
    (comp (ref "L0")
      (value "LEDSMT1206")
      (footprint "eagle-import:1206")
      (libsource (lib "eagle-import") (part "LEDSMT1206"))
    )
    (comp (ref "L1")
      (value "LEDSMT1206")
      (footprint "eagle-import:1206")
      (libsource (lib "eagle-import") (part "LEDSMT1206"))
    )
    (comp (ref "L2")
      (value "LEDSMT1206")
      (footprint "eagle-import:1206")
      (libsource (lib "eagle-import") (part "LEDSMT1206"))
    )
    (comp (ref "L3")
      (value "LEDSMT1206")
      (footprint "eagle-import:1206")
      (libsource (lib "eagle-import") (part "LEDSMT1206"))
    )
    (comp (ref "L4")
      (value "LEDSMT1206")
      (footprint "eagle-import:1206")
      (libsource (lib "eagle-import") (part "LEDSMT1206"))
    )
    (comp (ref "L5")
      (value "LEDSMT1206")
      (footprint "eagle-import:1206")
      (libsource (lib "eagle-import") (part "LEDSMT1206"))
    )
    (comp (ref "L6")
      (value "LEDSMT1206")
      (footprint "eagle-import:1206")
      (libsource (lib "eagle-import") (part "LEDSMT1206"))
    )
    (comp (ref "L7")
      (value "LEDSMT1206")
      (footprint "eagle-import:1206")
      (libsource (lib "eagle-import") (part "LEDSMT1206"))
    )
    (comp (ref "PH41")
      (value "PINHD-2X7")
      (footprint "eagle-import:2X07")
      (libsource (lib "eagle-import") (part "PINHD-2X7"))
    )
    (comp (ref "PH48")
      (value "PINHD-1X10")
      (footprint "eagle-import:1X10-BIG")
      (libsource (lib "eagle-import") (part "PINHD-1X10"))
    )
    (comp (ref "PH49")
      (value "PINHD-1X10")
      (footprint "eagle-import:1X10-BIG")
      (libsource (lib "eagle-import") (part "PINHD-1X10"))
    )
    (comp (ref "PH50")
      (value "PINHD-1X10")
      (footprint "eagle-import:1X10-BIG")
      (libsource (lib "eagle-import") (part "PINHD-1X10"))
    )
    (comp (ref "PH51")
      (value "PINHD-1X10")
      (footprint "eagle-import:1X10-BIG")
      (libsource (lib "eagle-import") (part "PINHD-1X10"))
    )
    (comp (ref "PH52")
      (value "PINHD-1X10")
      (footprint "eagle-import:1X10-BIG")
      (libsource (lib "eagle-import") (part "PINHD-1X10"))
    )
    (comp (ref "PH53")
      (value "PINHD-1X10")
      (footprint "eagle-import:1X10-BIG")
      (libsource (lib "eagle-import") (part "PINHD-1X10"))
    )
    (comp (ref "PH54")
      (value "PINHD-1X10")
      (footprint "eagle-import:1X10-BIG")
      (libsource (lib "eagle-import") (part "PINHD-1X10"))
    )
    (comp (ref "PH55")
      (value "PINHD-1X10")
      (footprint "eagle-import:1X10-BIG")
      (libsource (lib "eagle-import") (part "PINHD-1X10"))
    )
    (comp (ref "PH56")
      (value "PINHD-1X10")
      (footprint "eagle-import:1X10-BIG")
      (libsource (lib "eagle-import") (part "PINHD-1X10"))
    )
    (comp (ref "PH57")
      (value "PINHD-1X10")
      (footprint "eagle-import:1X10-BIG")
      (libsource (lib "eagle-import") (part "PINHD-1X10"))
    )
    (comp (ref "PH63")
      (value "MA08-2")
      (footprint "eagle-import:MA08-2")
      (libsource (lib "eagle-import") (part "MA08-2"))
    )
    (comp (ref "R1")
      (value "100")
      (footprint "eagle-import:R1206")
      (libsource (lib "eagle-import") (part "resistor_R-US_R1206"))
    )
    (comp (ref "R2")
      (value "100")
      (footprint "eagle-import:R1206")
      (libsource (lib "eagle-import") (part "resistor_R-US_R1206"))
    )
    (comp (ref "R3")
      (value "100")
      (footprint "eagle-import:R1206")
      (libsource (lib "eagle-import") (part "resistor_R-US_R1206"))
    )
    (comp (ref "R4")
      (value "470")
      (footprint "eagle-import:R1206")
      (libsource (lib "eagle-import") (part "resistor_R-US_R1206"))
    )
    (comp (ref "R5")
      (value "470")
      (footprint "eagle-import:R1206")
      (libsource (lib "eagle-import") (part "resistor_R-US_R1206"))
    )
    (comp (ref "R6")
      (value "470")
      (footprint "eagle-import:R1206")
      (libsource (lib "eagle-import") (part "resistor_R-US_R1206"))
    )
    (comp (ref "R7")
      (value "1K")
      (footprint "eagle-import:R1206")
      (libsource (lib "eagle-import") (part "resistor_R-US_R1206"))
    )
    (comp (ref "R8")
      (value "1K")
      (footprint "eagle-import:R1206")
      (libsource (lib "eagle-import") (part "resistor_R-US_R1206"))
    )
    (comp (ref "R9")
      (value "1K")
      (footprint "eagle-import:R1206")
      (libsource (lib "eagle-import") (part "resistor_R-US_R1206"))
    )
    (comp (ref "R10")
      (value "4.7K")
      (footprint "eagle-import:R1206")
      (libsource (lib "eagle-import") (part "resistor_R-US_R1206"))
    )
    (comp (ref "R11")
      (value "4.7K")
      (footprint "eagle-import:R1206")
      (libsource (lib "eagle-import") (part "resistor_R-US_R1206"))
    )
    (comp (ref "R12")
      (value "4.7K")
      (footprint "eagle-import:R1206")
      (libsource (lib "eagle-import") (part "resistor_R-US_R1206"))
    )
    (comp (ref "R13")
      (value "10K")
      (footprint "eagle-import:R1206")
      (libsource (lib "eagle-import") (part "resistor_R-US_R1206"))
    )
    (comp (ref "R14")
      (value "10K")
      (footprint "eagle-import:R1206")
      (libsource (lib "eagle-import") (part "resistor_R-US_R1206"))
    )
    (comp (ref "R15")
      (value "10K")
      (footprint "eagle-import:R1206")
      (libsource (lib "eagle-import") (part "resistor_R-US_R1206"))
    )
    (comp (ref "R16")
      (value "10K")
      (footprint "eagle-import:R1206")
      (libsource (lib "eagle-import") (part "resistor_R-US_R1206"))
    )
    (comp (ref "R17")
      (value "10K")
      (footprint "eagle-import:R1206")
      (libsource (lib "eagle-import") (part "resistor_R-US_R1206"))
    )
    (comp (ref "R18")
      (value "10K")
      (footprint "eagle-import:R1206")
      (libsource (lib "eagle-import") (part "resistor_R-US_R1206"))
    )
    (comp (ref "R19")
      (value "15K")
      (footprint "eagle-import:R1206")
      (libsource (lib "eagle-import") (part "resistor_R-US_R1206"))
    )
    (comp (ref "R20")
      (value "15K")
      (footprint "eagle-import:R1206")
      (libsource (lib "eagle-import") (part "resistor_R-US_R1206"))
    )
    (comp (ref "R21")
      (value "15K")
      (footprint "eagle-import:R1206")
      (libsource (lib "eagle-import") (part "resistor_R-US_R1206"))
    )
    (comp (ref "R22")
      (value "47K")
      (footprint "eagle-import:R1206")
      (libsource (lib "eagle-import") (part "resistor_R-US_R1206"))
    )
    (comp (ref "R23")
      (value "47K")
      (footprint "eagle-import:R1206")
      (libsource (lib "eagle-import") (part "resistor_R-US_R1206"))
    )
    (comp (ref "R24")
      (value "47K")
      (footprint "eagle-import:R1206")
      (libsource (lib "eagle-import") (part "resistor_R-US_R1206"))
    )
    (comp (ref "R25")
      (value "100K")
      (footprint "eagle-import:R1206")
      (libsource (lib "eagle-import") (part "resistor_R-US_R1206"))
    )
    (comp (ref "R26")
      (value "100K")
      (footprint "eagle-import:R1206")
      (libsource (lib "eagle-import") (part "resistor_R-US_R1206"))
    )
    (comp (ref "R27")
      (value "100K")
      (footprint "eagle-import:R1206")
      (libsource (lib "eagle-import") (part "resistor_R-US_R1206"))
    )
    (comp (ref "R28")
      (value "470K")
      (footprint "eagle-import:R1206")
      (libsource (lib "eagle-import") (part "resistor_R-US_R1206"))
    )
    (comp (ref "R29")
      (value "470K")
      (footprint "eagle-import:R1206")
      (libsource (lib "eagle-import") (part "resistor_R-US_R1206"))
    )
    (comp (ref "R30")
      (value "470K")
      (footprint "eagle-import:R1206")
      (libsource (lib "eagle-import") (part "resistor_R-US_R1206"))
    )
    (comp (ref "R31")
      (value "470")
      (footprint "eagle-import:R1206")
      (libsource (lib "eagle-import") (part "resistor_R-US_R1206"))
    )
    (comp (ref "R32")
      (value "330")
      (footprint "eagle-import:R1206")
      (libsource (lib "eagle-import") (part "resistor_R-US_R1206"))
    )
    (comp (ref "R33")
      (value "330")
      (footprint "eagle-import:R1206")
      (libsource (lib "eagle-import") (part "resistor_R-US_R1206"))
    )
    (comp (ref "R34")
      (value "330")
      (footprint "eagle-import:R1206")
      (libsource (lib "eagle-import") (part "resistor_R-US_R1206"))
    )
    (comp (ref "R35")
      (value "330")
      (footprint "eagle-import:R1206")
      (libsource (lib "eagle-import") (part "resistor_R-US_R1206"))
    )
    (comp (ref "R36")
      (value "330")
      (footprint "eagle-import:R1206")
      (libsource (lib "eagle-import") (part "resistor_R-US_R1206"))
    )
    (comp (ref "R37")
      (value "330")
      (footprint "eagle-import:R1206")
      (libsource (lib "eagle-import") (part "resistor_R-US_R1206"))
    )
    (comp (ref "R38")
      (value "330")
      (footprint "eagle-import:R1206")
      (libsource (lib "eagle-import") (part "resistor_R-US_R1206"))
    )
    (comp (ref "S1")
      (value "DPDT_JS202011CQN")
      (footprint "eagle-import:DPDT_JS202011CQN")
      (libsource (lib "eagle-import") (part "DPDT_JS202011CQN"))
    )
    (comp (ref "U1")
      (value "USB")
      (footprint "eagle-import:FCI-10103594-0001LF")
      (libsource (lib "eagle-import") (part "USB-RECEPTABLE"))
    )
    (comp (ref "U2")
      (value "USB-B")
      (footprint "eagle-import:USB-B-PTH")
      (libsource (lib "eagle-import") (part "USBPTH"))
    )
  )
  (nets
    (net (code "1") (name "+OUT") (class "Default")
      (node (ref "IC11") (pin "16") (pinfunction "+OUT_R_16") (pintype "output"))
      (node (ref "PH38") (pin "5") (pinfunction "5_5") (pintype "passive"))
    )
    (net (code "2") (name "-OUT") (class "Default")
      (node (ref "IC11") (pin "14") (pinfunction "-OUT_R_14") (pintype "output"))
      (node (ref "PH38") (pin "6") (pinfunction "6_6") (pintype "passive"))
    )
    (net (code "3") (name "3.3V") (class "Default")
      (node (ref "C32") (pin "1") (pinfunction "1_1") (pintype "passive"))
      (node (ref "C33") (pin "1") (pinfunction "1_1") (pintype "passive"))
      (node (ref "IC13") (pin "14") (pinfunction "VS_14") (pintype "bidirectional"))
      (node (ref "IC13") (pin "15") (pinfunction "VS_15") (pintype "bidirectional"))
      (node (ref "IC14") (pin "5") (pinfunction "OUT_5") (pintype "passive"))
    )
    (net (code "4") (name "A1A") (class "Default")
      (node (ref "AR1") (pin "9") (pinfunction "9_9") (pintype "bidirectional"))
      (node (ref "IC3") (pin "1") (pinfunction "1A_1") (pintype "input"))
      (node (ref "PH45") (pin "1") (pinfunction "1_1") (pintype "passive"))
    )
    (net (code "5") (name "A1B") (class "Default")
      (node (ref "AR1") (pin "8") (pinfunction "8_8") (pintype "bidirectional"))
      (node (ref "IC3") (pin "2") (pinfunction "1B_2") (pintype "input"))
      (node (ref "PH45") (pin "2") (pinfunction "2_2") (pintype "passive"))
    )
    (net (code "6") (name "A1Y") (class "Default")
      (node (ref "IC3") (pin "3") (pinfunction "1Y_3") (pintype "output"))
      (node (ref "PH36") (pin "1") (pinfunction "1_1") (pintype "passive"))
    )
    (net (code "7") (name "A2A") (class "Default")
      (node (ref "AR1") (pin "7") (pinfunction "7_7") (pintype "bidirectional"))
      (node (ref "IC3") (pin "4") (pinfunction "2A_4") (pintype "input"))
      (node (ref "PH45") (pin "3") (pinfunction "3_3") (pintype "passive"))
    )
    (net (code "8") (name "A2B") (class "Default")
      (node (ref "AR1") (pin "6") (pinfunction "6_6") (pintype "bidirectional"))
      (node (ref "IC3") (pin "5") (pinfunction "2B_5") (pintype "input"))
      (node (ref "PH45") (pin "4") (pinfunction "4_4") (pintype "passive"))
    )
    (net (code "9") (name "A2Y") (class "Default")
      (node (ref "IC3") (pin "6") (pinfunction "2Y_6") (pintype "output"))
      (node (ref "PH36") (pin "2") (pinfunction "2_2") (pintype "passive"))
    )
    (net (code "10") (name "A3A") (class "Default")
      (node (ref "AR1") (pin "1") (pinfunction "1_1") (pintype "bidirectional"))
      (node (ref "IC3") (pin "9") (pinfunction "3A_9") (pintype "input"))
      (node (ref "PH45") (pin "5") (pinfunction "5_5") (pintype "passive"))
    )
    (net (code "11") (name "A3B") (class "Default")
      (node (ref "AR1") (pin "2") (pinfunction "2_2") (pintype "bidirectional"))
      (node (ref "IC3") (pin "10") (pinfunction "3B_10") (pintype "input"))
      (node (ref "PH45") (pin "6") (pinfunction "6_6") (pintype "passive"))
    )
    (net (code "12") (name "A3Y") (class "Default")
      (node (ref "IC3") (pin "8") (pinfunction "3Y_8") (pintype "output"))
      (node (ref "PH36") (pin "3") (pinfunction "3_3") (pintype "passive"))
    )
    (net (code "13") (name "A4A") (class "Default")
      (node (ref "AR1") (pin "3") (pinfunction "3_3") (pintype "bidirectional"))
      (node (ref "IC3") (pin "12") (pinfunction "4A_12") (pintype "input"))
      (node (ref "PH45") (pin "7") (pinfunction "7_7") (pintype "passive"))
    )
    (net (code "14") (name "A4B") (class "Default")
      (node (ref "AR1") (pin "4") (pinfunction "4_4") (pintype "bidirectional"))
      (node (ref "IC3") (pin "13") (pinfunction "4B_13") (pintype "input"))
      (node (ref "PH45") (pin "8") (pinfunction "8_8") (pintype "passive"))
    )
    (net (code "15") (name "A4Y") (class "Default")
      (node (ref "IC3") (pin "11") (pinfunction "4Y_11") (pintype "output"))
      (node (ref "PH36") (pin "4") (pinfunction "4_4") (pintype "passive"))
    )
    (net (code "16") (name "B") (class "Default")
      (node (ref "JMP1") (pin "1") (pinfunction "1_1") (pintype "passive"))
      (node (ref "JMP4") (pin "1") (pinfunction "1_1") (pintype "passive"))
      (node (ref "PH11") (pin "3") (pinfunction "3_3") (pintype "passive"))
    )
    (net (code "17") (name "D0") (class "Default")
      (node (ref "PH41") (pin "1") (pinfunction "1_1") (pintype "passive"))
      (node (ref "PH63") (pin "1") (pinfunction "1_1") (pintype "passive"))
      (node (ref "R32") (pin "2") (pinfunction "2_2") (pintype "passive"))
    )
    (net (code "18") (name "D1") (class "Default")
      (node (ref "PH41") (pin "2") (pinfunction "2_2") (pintype "passive"))
      (node (ref "PH63") (pin "2") (pinfunction "2_2") (pintype "passive"))
    )
    (net (code "19") (name "D2") (class "Default")
      (node (ref "PH41") (pin "3") (pinfunction "3_3") (pintype "passive"))
      (node (ref "PH63") (pin "3") (pinfunction "3_3") (pintype "passive"))
      (node (ref "R33") (pin "2") (pinfunction "2_2") (pintype "passive"))
    )
    (net (code "20") (name "D3") (class "Default")
      (node (ref "PH41") (pin "4") (pinfunction "4_4") (pintype "passive"))
      (node (ref "PH63") (pin "4") (pinfunction "4_4") (pintype "passive"))
    )
    (net (code "21") (name "D4") (class "Default")
      (node (ref "PH41") (pin "5") (pinfunction "5_5") (pintype "passive"))
      (node (ref "PH63") (pin "5") (pinfunction "5_5") (pintype "passive"))
      (node (ref "R34") (pin "2") (pinfunction "2_2") (pintype "passive"))
    )
    (net (code "22") (name "D5") (class "Default")
      (node (ref "PH41") (pin "6") (pinfunction "6_6") (pintype "passive"))
      (node (ref "PH63") (pin "6") (pinfunction "6_6") (pintype "passive"))
    )
    (net (code "23") (name "D6") (class "Default")
      (node (ref "PH41") (pin "7") (pinfunction "7_7") (pintype "passive"))
      (node (ref "PH63") (pin "7") (pinfunction "7_7") (pintype "passive"))
      (node (ref "R35") (pin "2") (pinfunction "2_2") (pintype "passive"))
    )
    (net (code "24") (name "D7") (class "Default")
      (node (ref "PH41") (pin "8") (pinfunction "8_8") (pintype "passive"))
      (node (ref "PH63") (pin "8") (pinfunction "8_8") (pintype "passive"))
    )
    (net (code "25") (name "D8") (class "Default")
      (node (ref "PH41") (pin "9") (pinfunction "9_9") (pintype "passive"))
      (node (ref "PH63") (pin "9") (pinfunction "9_9") (pintype "passive"))
      (node (ref "R36") (pin "2") (pinfunction "2_2") (pintype "passive"))
    )
    (net (code "26") (name "D9") (class "Default")
      (node (ref "PH41") (pin "10") (pinfunction "10_10") (pintype "passive"))
      (node (ref "PH63") (pin "10") (pinfunction "10_10") (pintype "passive"))
    )
    (net (code "27") (name "D10") (class "Default")
      (node (ref "PH41") (pin "11") (pinfunction "11_11") (pintype "passive"))
      (node (ref "PH63") (pin "11") (pinfunction "11_11") (pintype "passive"))
      (node (ref "R37") (pin "2") (pinfunction "2_2") (pintype "passive"))
    )
    (net (code "28") (name "D11") (class "Default")
      (node (ref "PH41") (pin "12") (pinfunction "12_12") (pintype "passive"))
      (node (ref "PH63") (pin "12") (pinfunction "12_12") (pintype "passive"))
    )
    (net (code "29") (name "D12") (class "Default")
      (node (ref "PH41") (pin "13") (pinfunction "13_13") (pintype "passive"))
      (node (ref "PH63") (pin "13") (pinfunction "13_13") (pintype "passive"))
      (node (ref "R38") (pin "2") (pinfunction "2_2") (pintype "passive"))
    )
    (net (code "30") (name "D13") (class "Default")
      (node (ref "PH41") (pin "14") (pinfunction "14_14") (pintype "passive"))
      (node (ref "PH63") (pin "14") (pinfunction "14_14") (pintype "passive"))
    )
    (net (code "31") (name "DG1") (class "Default")
      (node (ref "DP1") (pin "9") (pinfunction "9_9") (pintype "bidirectional"))
      (node (ref "PH3") (pin "1") (pinfunction "1_1") (pintype "passive"))
    )
    (net (code "32") (name "DG2") (class "Default")
      (node (ref "DP1") (pin "4") (pinfunction "4_4") (pintype "bidirectional"))
      (node (ref "PH3") (pin "2") (pinfunction "2_2") (pintype "passive"))
    )
    (net (code "33") (name "DP") (class "Default")
      (node (ref "DP1") (pin "2") (pinfunction "2_2") (pintype "bidirectional"))
    )
    (net (code "34") (name "G") (class "Default")
      (node (ref "JMP3") (pin "1") (pinfunction "1_1") (pintype "passive"))
      (node (ref "JMP5") (pin "1") (pinfunction "1_1") (pintype "passive"))
      (node (ref "PH11") (pin "2") (pinfunction "2_2") (pintype "passive"))
    )
    (net (code "35") (name "GND") (class "Default")
      (node (ref "AR1") (pin "10") (pinfunction "10_10") (pintype "bidirectional"))
      (node (ref "AR1") (pin "5") (pinfunction "5_5") (pintype "bidirectional"))
      (node (ref "AR2") (pin "10") (pinfunction "10_10") (pintype "bidirectional"))
      (node (ref "AR2") (pin "5") (pinfunction "5_5") (pintype "bidirectional"))
      (node (ref "AR3") (pin "10") (pinfunction "10_10") (pintype "bidirectional"))
      (node (ref "AR3") (pin "5") (pinfunction "5_5") (pintype "bidirectional"))
      (node (ref "AR4") (pin "10") (pinfunction "10_10") (pintype "bidirectional"))
      (node (ref "AR4") (pin "5") (pinfunction "5_5") (pintype "bidirectional"))
      (node (ref "C21") (pin "2") (pinfunction "2_2") (pintype "passive"))
      (node (ref "C22") (pin "2") (pinfunction "2_2") (pintype "passive"))
      (node (ref "C23") (pin "2") (pinfunction "2_2") (pintype "passive"))
      (node (ref "C24") (pin "2") (pinfunction "2_2") (pintype "passive"))
      (node (ref "C25") (pin "2") (pinfunction "2_2") (pintype "passive"))
      (node (ref "C27") (pin "-") (pinfunction "-_-") (pintype "passive"))
      (node (ref "C29") (pin "2") (pinfunction "2_2") (pintype "passive"))
      (node (ref "C30") (pin "2") (pinfunction "2_2") (pintype "passive"))
      (node (ref "C31") (pin "2") (pinfunction "2_2") (pintype "passive"))
      (node (ref "C32") (pin "2") (pinfunction "2_2") (pintype "passive"))
      (node (ref "C33") (pin "2") (pinfunction "2_2") (pintype "passive"))
      (node (ref "C34") (pin "2") (pinfunction "2_2") (pintype "passive"))
      (node (ref "H1") (pin "B2,8") (pinfunction "MOUNT_B2,8") (pintype "passive"))
      (node (ref "H2") (pin "B2,8") (pinfunction "MOUNT_B2,8") (pintype "passive"))
      (node (ref "H3") (pin "B2,8") (pinfunction "MOUNT_B2,8") (pintype "passive"))
      (node (ref "H4") (pin "B2,8") (pinfunction "MOUNT_B2,8") (pintype "passive"))
      (node (ref "IC1") (pin "11") (pinfunction "GND_11") (pintype "passive"))
      (node (ref "IC10") (pin "GND") (pinfunction "GND_GND") (pintype "bidirectional"))
      (node (ref "IC10") (pin "RBI") (pinfunction "RBI_RBI") (pintype "bidirectional"))
      (node (ref "IC11") (pin "11") (pinfunction "GND_11") (pintype "output"))
      (node (ref "IC11") (pin "15") (pinfunction "PGND1_15") (pintype "output"))
      (node (ref "IC11") (pin "2") (pinfunction "PGND_2") (pintype "input"))
      (node (ref "IC11") (pin "9") (pinfunction "NC_9") (pintype "output"))
      (node (ref "IC12") (pin "11") (pinfunction "GND_11") (pintype "passive"))
      (node (ref "IC13") (pin "6") (pinfunction "GND_6") (pintype "bidirectional"))
      (node (ref "IC13") (pin "7") (pinfunction "GND_7") (pintype "bidirectional"))
      (node (ref "IC14") (pin "2") (pinfunction "GND_2") (pintype "input"))
      (node (ref "IC2") (pin "11") (pinfunction "GND_11") (pintype "passive"))
      (node (ref "IC3") (pin "7") (pinfunction "GND_7") (pintype "passive"))
      (node (ref "IC4") (pin "7") (pinfunction "GND_7") (pintype "passive"))
      (node (ref "IC5") (pin "7") (pinfunction "GND_7") (pintype "passive"))
      (node (ref "IC6") (pin "12") (pinfunction "R_12") (pintype "input"))
      (node (ref "IC6") (pin "4") (pinfunction "R_4") (pintype "input"))
      (node (ref "IC6") (pin "7") (pinfunction "S_7") (pintype "input"))
      (node (ref "IC6") (pin "8") (pinfunction "VSS_8") (pintype "power_in"))
      (node (ref "IC6") (pin "9") (pinfunction "S_9") (pintype "input"))
      (node (ref "IC7") (pin "12") (pinfunction "R_12") (pintype "input"))
      (node (ref "IC7") (pin "4") (pinfunction "R_4") (pintype "input"))
      (node (ref "IC7") (pin "7") (pinfunction "S_7") (pintype "input"))
      (node (ref "IC7") (pin "8") (pinfunction "VSS_8") (pintype "power_in"))
      (node (ref "IC7") (pin "9") (pinfunction "S_9") (pintype "input"))
      (node (ref "IC8") (pin "1") (pinfunction "GND_1") (pintype "power_in"))
      (node (ref "IC9") (pin "2") (pinfunction "GND_2") (pintype "bidirectional"))
      (node (ref "IC9") (pin "6") (pinfunction "TIME_6") (pintype "bidirectional"))
      (node (ref "JMP1") (pin "3") (pinfunction "3_3") (pintype "passive"))
      (node (ref "JMP2") (pin "3") (pinfunction "3_3") (pintype "passive"))
      (node (ref "JMP3") (pin "3") (pinfunction "3_3") (pintype "passive"))
      (node (ref "JMP4") (pin "3") (pinfunction "3_3") (pintype "passive"))
      (node (ref "JMP5") (pin "3") (pinfunction "3_3") (pintype "passive"))
      (node (ref "JMP6") (pin "3") (pinfunction "3_3") (pintype "passive"))
      (node (ref "L0") (pin "C") (pinfunction "C_C") (pintype "passive"))
      (node (ref "L1") (pin "C") (pinfunction "C_C") (pintype "passive"))
      (node (ref "L10") (pin "C") (pinfunction "C_C") (pintype "passive"))
      (node (ref "L11") (pin "C") (pinfunction "C_C") (pintype "passive"))
      (node (ref "L12") (pin "C") (pinfunction "C_C") (pintype "passive"))
      (node (ref "L13") (pin "C") (pinfunction "C_C") (pintype "passive"))
      (node (ref "L14") (pin "C") (pinfunction "C_C") (pintype "passive"))
      (node (ref "L15") (pin "C") (pinfunction "C_C") (pintype "passive"))
      (node (ref "L16") (pin "C") (pinfunction "C_C") (pintype "passive"))
      (node (ref "L2") (pin "C") (pinfunction "C_C") (pintype "passive"))
      (node (ref "L3") (pin "C") (pinfunction "C_C") (pintype "passive"))
      (node (ref "L4") (pin "C") (pinfunction "C_C") (pintype "passive"))
      (node (ref "L5") (pin "C") (pinfunction "C_C") (pintype "passive"))
      (node (ref "L6") (pin "C") (pinfunction "C_C") (pintype "passive"))
      (node (ref "L7") (pin "C") (pinfunction "C_C") (pintype "passive"))
      (node (ref "L8") (pin "C") (pinfunction "C_C") (pintype "passive"))
      (node (ref "L9") (pin "C") (pinfunction "C_C") (pintype "passive"))
      (node (ref "PH38") (pin "2") (pinfunction "2_2") (pintype "passive"))
      (node (ref "PH38") (pin "4") (pinfunction "4_4") (pintype "passive"))
      (node (ref "PH62") (pin "1") (pinfunction "1_1") (pintype "passive"))
      (node (ref "PH62") (pin "10") (pinfunction "10_10") (pintype "passive"))
      (node (ref "PH62") (pin "11") (pinfunction "11_11") (pintype "passive"))
      (node (ref "PH62") (pin "12") (pinfunction "12_12") (pintype "passive"))
      (node (ref "PH62") (pin "13") (pinfunction "13_13") (pintype "passive"))
      (node (ref "PH62") (pin "14") (pinfunction "14_14") (pintype "passive"))
      (node (ref "PH62") (pin "15") (pinfunction "15_15") (pintype "passive"))
      (node (ref "PH62") (pin "16") (pinfunction "16_16") (pintype "passive"))
      (node (ref "PH62") (pin "17") (pinfunction "17_17") (pintype "passive"))
      (node (ref "PH62") (pin "18") (pinfunction "18_18") (pintype "passive"))
      (node (ref "PH62") (pin "19") (pinfunction "19_19") (pintype "passive"))
      (node (ref "PH62") (pin "2") (pinfunction "2_2") (pintype "passive"))
      (node (ref "PH62") (pin "20") (pinfunction "20_20") (pintype "passive"))
      (node (ref "PH62") (pin "21") (pinfunction "21_21") (pintype "passive"))
      (node (ref "PH62") (pin "22") (pinfunction "22_22") (pintype "passive"))
      (node (ref "PH62") (pin "23") (pinfunction "23_23") (pintype "passive"))
      (node (ref "PH62") (pin "24") (pinfunction "24_24") (pintype "passive"))
      (node (ref "PH62") (pin "25") (pinfunction "25_25") (pintype "passive"))
      (node (ref "PH62") (pin "26") (pinfunction "26_26") (pintype "passive"))
      (node (ref "PH62") (pin "27") (pinfunction "27_27") (pintype "passive"))
      (node (ref "PH62") (pin "28") (pinfunction "28_28") (pintype "passive"))
      (node (ref "PH62") (pin "29") (pinfunction "29_29") (pintype "passive"))
      (node (ref "PH62") (pin "3") (pinfunction "3_3") (pintype "passive"))
      (node (ref "PH62") (pin "30") (pinfunction "30_30") (pintype "passive"))
      (node (ref "PH62") (pin "4") (pinfunction "4_4") (pintype "passive"))
      (node (ref "PH62") (pin "5") (pinfunction "5_5") (pintype "passive"))
      (node (ref "PH62") (pin "6") (pinfunction "6_6") (pintype "passive"))
      (node (ref "PH62") (pin "7") (pinfunction "7_7") (pintype "passive"))
      (node (ref "PH62") (pin "8") (pinfunction "8_8") (pintype "passive"))
      (node (ref "PH62") (pin "9") (pinfunction "9_9") (pintype "passive"))
      (node (ref "PH63") (pin "16") (pinfunction "16_16") (pintype "passive"))
      (node (ref "R39") (pin "1") (pinfunction "1_1") (pintype "passive"))
      (node (ref "R40") (pin "1") (pinfunction "1_1") (pintype "passive"))
      (node (ref "R64") (pin "2") (pinfunction "2_2") (pintype "passive"))
      (node (ref "R65") (pin "2") (pinfunction "2_2") (pintype "passive"))
      (node (ref "R66") (pin "2") (pinfunction "2_2") (pintype "passive"))
      (node (ref "U1") (pin "5") (pinfunction "GND_5") (pintype "bidirectional"))
      (node (ref "U2") (pin "GND") (pinfunction "GND_GND") (pintype "bidirectional"))
    )
    (net (code "36") (name "I1A") (class "Default")
      (node (ref "AR3") (pin "9") (pinfunction "9_9") (pintype "bidirectional"))
      (node (ref "IC5") (pin "1") (pinfunction "1A_1") (pintype "input"))
      (node (ref "PH39") (pin "1") (pinfunction "1_1") (pintype "passive"))
    )
    (net (code "37") (name "I1Y") (class "Default")
      (node (ref "IC5") (pin "2") (pinfunction "1Y_2") (pintype "output"))
      (node (ref "PH40") (pin "1") (pinfunction "1_1") (pintype "passive"))
    )
    (net (code "38") (name "I2A") (class "Default")
      (node (ref "AR3") (pin "3") (pinfunction "3_3") (pintype "bidirectional"))
      (node (ref "IC5") (pin "3") (pinfunction "2A_3") (pintype "input"))
      (node (ref "PH39") (pin "2") (pinfunction "2_2") (pintype "passive"))
    )
    (net (code "39") (name "I2Y") (class "Default")
      (node (ref "IC5") (pin "4") (pinfunction "2Y_4") (pintype "output"))
      (node (ref "PH40") (pin "2") (pinfunction "2_2") (pintype "passive"))
    )
    (net (code "40") (name "I3A") (class "Default")
      (node (ref "AR3") (pin "7") (pinfunction "7_7") (pintype "bidirectional"))
      (node (ref "IC5") (pin "5") (pinfunction "3A_5") (pintype "input"))
      (node (ref "PH39") (pin "3") (pinfunction "3_3") (pintype "passive"))
    )
    (net (code "41") (name "I3Y") (class "Default")
      (node (ref "IC5") (pin "6") (pinfunction "3Y_6") (pintype "output"))
      (node (ref "PH40") (pin "3") (pinfunction "3_3") (pintype "passive"))
    )
    (net (code "42") (name "I4A") (class "Default")
      (node (ref "AR3") (pin "6") (pinfunction "6_6") (pintype "bidirectional"))
      (node (ref "IC5") (pin "9") (pinfunction "4A_9") (pintype "input"))
      (node (ref "PH39") (pin "4") (pinfunction "4_4") (pintype "passive"))
    )
    (net (code "43") (name "I4Y") (class "Default")
      (node (ref "IC5") (pin "8") (pinfunction "4Y_8") (pintype "output"))
      (node (ref "PH40") (pin "4") (pinfunction "4_4") (pintype "passive"))
    )
    (net (code "44") (name "I5A") (class "Default")
      (node (ref "AR3") (pin "1") (pinfunction "1_1") (pintype "bidirectional"))
      (node (ref "IC5") (pin "11") (pinfunction "5A_11") (pintype "input"))
      (node (ref "PH39") (pin "5") (pinfunction "5_5") (pintype "passive"))
    )
    (net (code "45") (name "I5Y") (class "Default")
      (node (ref "IC5") (pin "10") (pinfunction "5Y_10") (pintype "output"))
      (node (ref "PH40") (pin "5") (pinfunction "5_5") (pintype "passive"))
    )
    (net (code "46") (name "I6A") (class "Default")
      (node (ref "AR3") (pin "2") (pinfunction "2_2") (pintype "bidirectional"))
      (node (ref "IC5") (pin "13") (pinfunction "6A_13") (pintype "input"))
      (node (ref "PH39") (pin "6") (pinfunction "6_6") (pintype "passive"))
    )
    (net (code "47") (name "I6Y") (class "Default")
      (node (ref "IC5") (pin "12") (pinfunction "6Y_12") (pintype "output"))
      (node (ref "PH40") (pin "6") (pinfunction "6_6") (pintype "passive"))
    )
    (net (code "48") (name "IA") (class "Default")
      (node (ref "AR4") (pin "9") (pinfunction "9_9") (pintype "bidirectional"))
      (node (ref "IC10") (pin "IA") (pinfunction "IA_IA") (pintype "bidirectional"))
      (node (ref "PH35") (pin "1") (pinfunction "1_1") (pintype "passive"))
    )
    (net (code "49") (name "IB") (class "Default")
      (node (ref "AR4") (pin "8") (pinfunction "8_8") (pintype "bidirectional"))
      (node (ref "IC10") (pin "IB") (pinfunction "IB_IB") (pintype "bidirectional"))
      (node (ref "PH35") (pin "2") (pinfunction "2_2") (pintype "passive"))
    )
    (net (code "50") (name "IC") (class "Default")
      (node (ref "AR4") (pin "7") (pinfunction "7_7") (pintype "bidirectional"))
      (node (ref "IC10") (pin "IC") (pinfunction "IC_IC") (pintype "bidirectional"))
      (node (ref "PH35") (pin "3") (pinfunction "3_3") (pintype "passive"))
    )
    (net (code "51") (name "ID") (class "Default")
      (node (ref "AR4") (pin "6") (pinfunction "6_6") (pintype "bidirectional"))
      (node (ref "IC10") (pin "ID") (pinfunction "ID_ID") (pintype "bidirectional"))
      (node (ref "PH35") (pin "4") (pinfunction "4_4") (pintype "passive"))
    )
    (net (code "52") (name "IN") (class "Default")
      (node (ref "C26") (pin "1") (pinfunction "1_1") (pintype "passive"))
      (node (ref "PH38") (pin "1") (pinfunction "1_1") (pintype "passive"))
    )
    (net (code "53") (name "INR") (class "Default")
      (node (ref "IC11") (pin "10") (pinfunction "INR_10") (pintype "output"))
      (node (ref "R60") (pin "1") (pinfunction "1_1") (pintype "passive"))
    )
    (net (code "54") (name "L1") (class "Default")
      (node (ref "PH47") (pin "9") (pinfunction "9_9") (pintype "passive"))
      (node (ref "R48") (pin "2") (pinfunction "2_2") (pintype "passive"))
    )
    (net (code "55") (name "L2") (class "Default")
      (node (ref "PH47") (pin "8") (pinfunction "8_8") (pintype "passive"))
      (node (ref "R49") (pin "2") (pinfunction "2_2") (pintype "passive"))
    )
    (net (code "56") (name "L3") (class "Default")
      (node (ref "PH47") (pin "7") (pinfunction "7_7") (pintype "passive"))
      (node (ref "R50") (pin "2") (pinfunction "2_2") (pintype "passive"))
    )
    (net (code "57") (name "L4") (class "Default")
      (node (ref "PH47") (pin "6") (pinfunction "6_6") (pintype "passive"))
      (node (ref "R51") (pin "2") (pinfunction "2_2") (pintype "passive"))
    )
    (net (code "58") (name "L5") (class "Default")
      (node (ref "PH47") (pin "5") (pinfunction "5_5") (pintype "passive"))
      (node (ref "R52") (pin "2") (pinfunction "2_2") (pintype "passive"))
    )
    (net (code "59") (name "L6") (class "Default")
      (node (ref "PH47") (pin "4") (pinfunction "4_4") (pintype "passive"))
      (node (ref "R53") (pin "2") (pinfunction "2_2") (pintype "passive"))
    )
    (net (code "60") (name "L7") (class "Default")
      (node (ref "PH47") (pin "3") (pinfunction "3_3") (pintype "passive"))
      (node (ref "R54") (pin "2") (pinfunction "2_2") (pintype "passive"))
    )
    (net (code "61") (name "L8") (class "Default")
      (node (ref "PH47") (pin "2") (pinfunction "2_2") (pintype "passive"))
      (node (ref "R55") (pin "2") (pinfunction "2_2") (pintype "passive"))
    )
    (net (code "62") (name "L9") (class "Default")
      (node (ref "PH47") (pin "1") (pinfunction "1_1") (pintype "passive"))
      (node (ref "R56") (pin "2") (pinfunction "2_2") (pintype "passive"))
    )
    (net (code "63") (name "MUTE") (class "Default")
      (node (ref "IC11") (pin "5") (pinfunction "MUTE_5") (pintype "input"))
    )
    (net (code "64") (name "Net-(C1-Pad1)") (class "Default")
      (node (ref "C1") (pin "1") (pinfunction "1_1") (pintype "passive"))
      (node (ref "PH56") (pin "10") (pinfunction "10_10") (pintype "passive"))
    )
    (net (code "65") (name "Net-(C1-Pad2)") (class "Default")
      (node (ref "C1") (pin "2") (pinfunction "2_2") (pintype "passive"))
      (node (ref "PH57") (pin "1") (pinfunction "1_1") (pintype "passive"))
    )
    (net (code "66") (name "Net-(C2-Pad1)") (class "Default")
      (node (ref "C2") (pin "1") (pinfunction "1_1") (pintype "passive"))
      (node (ref "PH54") (pin "10") (pinfunction "10_10") (pintype "passive"))
    )
    (net (code "67") (name "Net-(C2-Pad2)") (class "Default")
      (node (ref "C2") (pin "2") (pinfunction "2_2") (pintype "passive"))
      (node (ref "PH55") (pin "1") (pinfunction "1_1") (pintype "passive"))
    )
    (net (code "68") (name "Net-(C3-Pad1)") (class "Default")
      (node (ref "C3") (pin "1") (pinfunction "1_1") (pintype "passive"))
      (node (ref "PH56") (pin "9") (pinfunction "9_9") (pintype "passive"))
    )
    (net (code "69") (name "Net-(C3-Pad2)") (class "Default")
      (node (ref "C3") (pin "2") (pinfunction "2_2") (pintype "passive"))
      (node (ref "PH57") (pin "2") (pinfunction "2_2") (pintype "passive"))
    )
    (net (code "70") (name "Net-(C4-Pad1)") (class "Default")
      (node (ref "C4") (pin "1") (pinfunction "1_1") (pintype "passive"))
      (node (ref "PH54") (pin "9") (pinfunction "9_9") (pintype "passive"))
    )
    (net (code "71") (name "Net-(C4-Pad2)") (class "Default")
      (node (ref "C4") (pin "2") (pinfunction "2_2") (pintype "passive"))
      (node (ref "PH55") (pin "2") (pinfunction "2_2") (pintype "passive"))
    )
    (net (code "72") (name "Net-(C5-Pad1)") (class "Default")
      (node (ref "C5") (pin "1") (pinfunction "1_1") (pintype "passive"))
      (node (ref "PH56") (pin "8") (pinfunction "8_8") (pintype "passive"))
    )
    (net (code "73") (name "Net-(C5-Pad2)") (class "Default")
      (node (ref "C5") (pin "2") (pinfunction "2_2") (pintype "passive"))
      (node (ref "PH57") (pin "3") (pinfunction "3_3") (pintype "passive"))
    )
    (net (code "74") (name "Net-(C6-Pad1)") (class "Default")
      (node (ref "C6") (pin "1") (pinfunction "1_1") (pintype "passive"))
      (node (ref "PH54") (pin "8") (pinfunction "8_8") (pintype "passive"))
    )
    (net (code "75") (name "Net-(C6-Pad2)") (class "Default")
      (node (ref "C6") (pin "2") (pinfunction "2_2") (pintype "passive"))
      (node (ref "PH55") (pin "3") (pinfunction "3_3") (pintype "passive"))
    )
    (net (code "76") (name "Net-(C7-Pad1)") (class "Default")
      (node (ref "C7") (pin "1") (pinfunction "1_1") (pintype "passive"))
      (node (ref "PH56") (pin "7") (pinfunction "7_7") (pintype "passive"))
    )
    (net (code "77") (name "Net-(C7-Pad2)") (class "Default")
      (node (ref "C7") (pin "2") (pinfunction "2_2") (pintype "passive"))
      (node (ref "PH57") (pin "4") (pinfunction "4_4") (pintype "passive"))
    )
    (net (code "78") (name "Net-(C8-Pad1)") (class "Default")
      (node (ref "C8") (pin "1") (pinfunction "1_1") (pintype "passive"))
      (node (ref "PH54") (pin "7") (pinfunction "7_7") (pintype "passive"))
    )
    (net (code "79") (name "Net-(C8-Pad2)") (class "Default")
      (node (ref "C8") (pin "2") (pinfunction "2_2") (pintype "passive"))
      (node (ref "PH55") (pin "4") (pinfunction "4_4") (pintype "passive"))
    )
    (net (code "80") (name "Net-(C9-Pad1)") (class "Default")
      (node (ref "C9") (pin "1") (pinfunction "1_1") (pintype "passive"))
      (node (ref "PH56") (pin "6") (pinfunction "6_6") (pintype "passive"))
    )
    (net (code "81") (name "Net-(C9-Pad2)") (class "Default")
      (node (ref "C9") (pin "2") (pinfunction "2_2") (pintype "passive"))
      (node (ref "PH57") (pin "5") (pinfunction "5_5") (pintype "passive"))
    )
    (net (code "82") (name "Net-(C10-Pad1)") (class "Default")
      (node (ref "C10") (pin "1") (pinfunction "1_1") (pintype "passive"))
      (node (ref "PH54") (pin "6") (pinfunction "6_6") (pintype "passive"))
    )
    (net (code "83") (name "Net-(C10-Pad2)") (class "Default")
      (node (ref "C10") (pin "2") (pinfunction "2_2") (pintype "passive"))
      (node (ref "PH55") (pin "5") (pinfunction "5_5") (pintype "passive"))
    )
    (net (code "84") (name "Net-(C11-Pad1)") (class "Default")
      (node (ref "C11") (pin "1") (pinfunction "1_1") (pintype "passive"))
      (node (ref "PH56") (pin "5") (pinfunction "5_5") (pintype "passive"))
    )
    (net (code "85") (name "Net-(C11-Pad2)") (class "Default")
      (node (ref "C11") (pin "2") (pinfunction "2_2") (pintype "passive"))
      (node (ref "PH57") (pin "6") (pinfunction "6_6") (pintype "passive"))
    )
    (net (code "86") (name "Net-(C12-Pad1)") (class "Default")
      (node (ref "C12") (pin "1") (pinfunction "1_1") (pintype "passive"))
      (node (ref "PH54") (pin "5") (pinfunction "5_5") (pintype "passive"))
    )
    (net (code "87") (name "Net-(C12-Pad2)") (class "Default")
      (node (ref "C12") (pin "2") (pinfunction "2_2") (pintype "passive"))
      (node (ref "PH55") (pin "6") (pinfunction "6_6") (pintype "passive"))
    )
    (net (code "88") (name "Net-(C13-Pad1)") (class "Default")
      (node (ref "C13") (pin "1") (pinfunction "1_1") (pintype "passive"))
      (node (ref "PH56") (pin "4") (pinfunction "4_4") (pintype "passive"))
    )
    (net (code "89") (name "Net-(C13-Pad2)") (class "Default")
      (node (ref "C13") (pin "2") (pinfunction "2_2") (pintype "passive"))
      (node (ref "PH57") (pin "7") (pinfunction "7_7") (pintype "passive"))
    )
    (net (code "90") (name "Net-(C14-Pad1)") (class "Default")
      (node (ref "C14") (pin "1") (pinfunction "1_1") (pintype "passive"))
      (node (ref "PH54") (pin "4") (pinfunction "4_4") (pintype "passive"))
    )
    (net (code "91") (name "Net-(C14-Pad2)") (class "Default")
      (node (ref "C14") (pin "2") (pinfunction "2_2") (pintype "passive"))
      (node (ref "PH55") (pin "7") (pinfunction "7_7") (pintype "passive"))
    )
    (net (code "92") (name "Net-(C15-Pad1)") (class "Default")
      (node (ref "C15") (pin "1") (pinfunction "1_1") (pintype "passive"))
      (node (ref "PH56") (pin "3") (pinfunction "3_3") (pintype "passive"))
    )
    (net (code "93") (name "Net-(C15-Pad2)") (class "Default")
      (node (ref "C15") (pin "2") (pinfunction "2_2") (pintype "passive"))
      (node (ref "PH57") (pin "8") (pinfunction "8_8") (pintype "passive"))
    )
    (net (code "94") (name "Net-(C16-Pad1)") (class "Default")
      (node (ref "C16") (pin "1") (pinfunction "1_1") (pintype "passive"))
      (node (ref "PH54") (pin "3") (pinfunction "3_3") (pintype "passive"))
    )
    (net (code "95") (name "Net-(C16-Pad2)") (class "Default")
      (node (ref "C16") (pin "2") (pinfunction "2_2") (pintype "passive"))
      (node (ref "PH55") (pin "8") (pinfunction "8_8") (pintype "passive"))
    )
    (net (code "96") (name "Net-(C17-Pad+)") (class "Default")
      (node (ref "C17") (pin "+") (pinfunction "+_+") (pintype "passive"))
      (node (ref "PH56") (pin "2") (pinfunction "2_2") (pintype "passive"))
    )
    (net (code "97") (name "Net-(C17-Pad-)") (class "Default")
      (node (ref "C17") (pin "-") (pinfunction "-_-") (pintype "passive"))
      (node (ref "PH57") (pin "9") (pinfunction "9_9") (pintype "passive"))
    )
    (net (code "98") (name "Net-(C18-Pad+)") (class "Default")
      (node (ref "C18") (pin "+") (pinfunction "+_+") (pintype "passive"))
      (node (ref "PH54") (pin "2") (pinfunction "2_2") (pintype "passive"))
    )
    (net (code "99") (name "Net-(C18-Pad-)") (class "Default")
      (node (ref "C18") (pin "-") (pinfunction "-_-") (pintype "passive"))
      (node (ref "PH55") (pin "9") (pinfunction "9_9") (pintype "passive"))
    )
    (net (code "100") (name "Net-(C19-Pad+)") (class "Default")
      (node (ref "C19") (pin "+") (pinfunction "+_+") (pintype "passive"))
      (node (ref "PH56") (pin "1") (pinfunction "1_1") (pintype "passive"))
    )
    (net (code "101") (name "Net-(C19-Pad-)") (class "Default")
      (node (ref "C19") (pin "-") (pinfunction "-_-") (pintype "passive"))
      (node (ref "PH57") (pin "10") (pinfunction "10_10") (pintype "passive"))
    )
    (net (code "102") (name "Net-(C20-Pad+)") (class "Default")
      (node (ref "C20") (pin "+") (pinfunction "+_+") (pintype "passive"))
      (node (ref "PH54") (pin "1") (pinfunction "1_1") (pintype "passive"))
    )
    (net (code "103") (name "Net-(C20-Pad-)") (class "Default")
      (node (ref "C20") (pin "-") (pinfunction "-_-") (pintype "passive"))
      (node (ref "PH55") (pin "10") (pinfunction "10_10") (pintype "passive"))
    )
    (net (code "104") (name "Net-(C26-Pad2)") (class "Default")
      (node (ref "C26") (pin "2") (pinfunction "2_2") (pintype "passive"))
      (node (ref "R60") (pin "2") (pinfunction "2_2") (pintype "passive"))
    )
    (net (code "105") (name "Net-(D1-Pad+)") (class "Default")
      (node (ref "D1") (pin "+") (pinfunction "+_+") (pintype "passive"))
      (node (ref "PH32") (pin "1") (pinfunction "1_1") (pintype "passive"))
    )
    (net (code "106") (name "Net-(D1-Pad-)") (class "Default")
      (node (ref "D1") (pin "-") (pinfunction "-_-") (pintype "passive"))
      (node (ref "PH33") (pin "1") (pinfunction "1_1") (pintype "passive"))
    )
    (net (code "107") (name "Net-(D2-Pad+)") (class "Default")
      (node (ref "D2") (pin "+") (pinfunction "+_+") (pintype "passive"))
      (node (ref "PH32") (pin "2") (pinfunction "2_2") (pintype "passive"))
    )
    (net (code "108") (name "Net-(D2-Pad-)") (class "Default")
      (node (ref "D2") (pin "-") (pinfunction "-_-") (pintype "passive"))
      (node (ref "PH33") (pin "2") (pinfunction "2_2") (pintype "passive"))
    )
    (net (code "109") (name "Net-(D3-Pad+)") (class "Default")
      (node (ref "D3") (pin "+") (pinfunction "+_+") (pintype "passive"))
      (node (ref "PH32") (pin "3") (pinfunction "3_3") (pintype "passive"))
    )
    (net (code "110") (name "Net-(D3-Pad-)") (class "Default")
      (node (ref "D3") (pin "-") (pinfunction "-_-") (pintype "passive"))
      (node (ref "PH33") (pin "3") (pinfunction "3_3") (pintype "passive"))
    )
    (net (code "111") (name "Net-(D4-Pad+)") (class "Default")
      (node (ref "D4") (pin "+") (pinfunction "+_+") (pintype "passive"))
      (node (ref "PH32") (pin "4") (pinfunction "4_4") (pintype "passive"))
    )
    (net (code "112") (name "Net-(D4-Pad-)") (class "Default")
      (node (ref "D4") (pin "-") (pinfunction "-_-") (pintype "passive"))
      (node (ref "PH33") (pin "4") (pinfunction "4_4") (pintype "passive"))
    )
    (net (code "113") (name "Net-(IC1-1IN+)") (class "Default")
      (node (ref "IC1") (pin "3") (pinfunction "1IN+_3") (pintype "input"))
      (node (ref "PH42") (pin "8") (pinfunction "8_8") (pintype "passive"))
    )
    (net (code "114") (name "Net-(IC1-1IN-)") (class "Default")
      (node (ref "IC1") (pin "2") (pinfunction "1IN-_2") (pintype "input"))
      (node (ref "PH42") (pin "7") (pinfunction "7_7") (pintype "passive"))
    )
    (net (code "115") (name "Net-(IC1-1OUT)") (class "Default")
      (node (ref "IC1") (pin "1") (pinfunction "1OUT_1") (pintype "output"))
      (node (ref "PH44") (pin "5") (pinfunction "5_5") (pintype "passive"))
    )
    (net (code "116") (name "Net-(IC1-2IN+)") (class "Default")
      (node (ref "IC1") (pin "5") (pinfunction "2IN+_5") (pintype "input"))
      (node (ref "PH42") (pin "6") (pinfunction "6_6") (pintype "passive"))
    )
    (net (code "117") (name "Net-(IC1-2IN-)") (class "Default")
      (node (ref "IC1") (pin "6") (pinfunction "2IN-_6") (pintype "input"))
      (node (ref "PH42") (pin "5") (pinfunction "5_5") (pintype "passive"))
    )
    (net (code "118") (name "Net-(IC1-2OUT)") (class "Default")
      (node (ref "IC1") (pin "7") (pinfunction "2OUT_7") (pintype "output"))
      (node (ref "PH44") (pin "6") (pinfunction "6_6") (pintype "passive"))
    )
    (net (code "119") (name "Net-(IC1-3IN+)") (class "Default")
      (node (ref "IC1") (pin "10") (pinfunction "3IN+_10") (pintype "input"))
      (node (ref "PH42") (pin "4") (pinfunction "4_4") (pintype "passive"))
    )
    (net (code "120") (name "Net-(IC1-3IN-)") (class "Default")
      (node (ref "IC1") (pin "9") (pinfunction "3IN-_9") (pintype "input"))
      (node (ref "PH42") (pin "3") (pinfunction "3_3") (pintype "passive"))
    )
    (net (code "121") (name "Net-(IC1-3OUT)") (class "Default")
      (node (ref "IC1") (pin "8") (pinfunction "3OUT_8") (pintype "output"))
      (node (ref "PH44") (pin "7") (pinfunction "7_7") (pintype "passive"))
    )
    (net (code "122") (name "Net-(IC1-4IN+)") (class "Default")
      (node (ref "IC1") (pin "12") (pinfunction "4IN+_12") (pintype "input"))
      (node (ref "PH42") (pin "2") (pinfunction "2_2") (pintype "passive"))
    )
    (net (code "123") (name "Net-(IC1-4IN-)") (class "Default")
      (node (ref "IC1") (pin "13") (pinfunction "4IN-_13") (pintype "input"))
      (node (ref "PH42") (pin "1") (pinfunction "1_1") (pintype "passive"))
    )
    (net (code "124") (name "Net-(IC1-4OUT)") (class "Default")
      (node (ref "IC1") (pin "14") (pinfunction "4OUT_14") (pintype "output"))
      (node (ref "PH44") (pin "8") (pinfunction "8_8") (pintype "passive"))
    )
    (net (code "125") (name "Net-(IC2-1IN+)") (class "Default")
      (node (ref "IC2") (pin "3") (pinfunction "1IN+_3") (pintype "input"))
      (node (ref "PH43") (pin "8") (pinfunction "8_8") (pintype "passive"))
    )
    (net (code "126") (name "Net-(IC2-1IN-)") (class "Default")
      (node (ref "IC2") (pin "2") (pinfunction "1IN-_2") (pintype "input"))
      (node (ref "PH43") (pin "7") (pinfunction "7_7") (pintype "passive"))
    )
    (net (code "127") (name "Net-(IC2-1OUT)") (class "Default")
      (node (ref "IC2") (pin "1") (pinfunction "1OUT_1") (pintype "output"))
      (node (ref "PH44") (pin "1") (pinfunction "1_1") (pintype "passive"))
    )
    (net (code "128") (name "Net-(IC2-2IN+)") (class "Default")
      (node (ref "IC2") (pin "5") (pinfunction "2IN+_5") (pintype "input"))
      (node (ref "PH43") (pin "6") (pinfunction "6_6") (pintype "passive"))
    )
    (net (code "129") (name "Net-(IC2-2IN-)") (class "Default")
      (node (ref "IC2") (pin "6") (pinfunction "2IN-_6") (pintype "input"))
      (node (ref "PH43") (pin "5") (pinfunction "5_5") (pintype "passive"))
    )
    (net (code "130") (name "Net-(IC2-2OUT)") (class "Default")
      (node (ref "IC2") (pin "7") (pinfunction "2OUT_7") (pintype "output"))
      (node (ref "PH44") (pin "2") (pinfunction "2_2") (pintype "passive"))
    )
    (net (code "131") (name "Net-(IC2-3IN+)") (class "Default")
      (node (ref "IC2") (pin "10") (pinfunction "3IN+_10") (pintype "input"))
      (node (ref "PH43") (pin "4") (pinfunction "4_4") (pintype "passive"))
    )
    (net (code "132") (name "Net-(IC2-3IN-)") (class "Default")
      (node (ref "IC2") (pin "9") (pinfunction "3IN-_9") (pintype "input"))
      (node (ref "PH43") (pin "3") (pinfunction "3_3") (pintype "passive"))
    )
    (net (code "133") (name "Net-(IC2-3OUT)") (class "Default")
      (node (ref "IC2") (pin "8") (pinfunction "3OUT_8") (pintype "output"))
      (node (ref "PH44") (pin "3") (pinfunction "3_3") (pintype "passive"))
    )
    (net (code "134") (name "Net-(IC2-4IN+)") (class "Default")
      (node (ref "IC2") (pin "12") (pinfunction "4IN+_12") (pintype "input"))
      (node (ref "PH43") (pin "2") (pinfunction "2_2") (pintype "passive"))
    )
    (net (code "135") (name "Net-(IC2-4IN-)") (class "Default")
      (node (ref "IC2") (pin "13") (pinfunction "4IN-_13") (pintype "input"))
      (node (ref "PH43") (pin "1") (pinfunction "1_1") (pintype "passive"))
    )
    (net (code "136") (name "Net-(IC2-4OUT)") (class "Default")
      (node (ref "IC2") (pin "14") (pinfunction "4OUT_14") (pintype "output"))
      (node (ref "PH44") (pin "4") (pinfunction "4_4") (pintype "passive"))
    )
    (net (code "137") (name "Net-(IC6A-CLK)") (class "Default")
      (node (ref "IC6") (pin "3") (pinfunction "CLK_3") (pintype "input"))
      (node (ref "PH27") (pin "2") (pinfunction "2_2") (pintype "passive"))
    )
    (net (code "138") (name "Net-(IC6A-J)") (class "Default")
      (node (ref "IC6") (pin "6") (pinfunction "J_6") (pintype "input"))
      (node (ref "PH27") (pin "3") (pinfunction "3_3") (pintype "passive"))
    )
    (net (code "139") (name "Net-(IC6A-K)") (class "Default")
      (node (ref "IC6") (pin "5") (pinfunction "K_5") (pintype "input"))
      (node (ref "PH27") (pin "1") (pinfunction "1_1") (pintype "passive"))
    )
    (net (code "140") (name "Net-(IC6A-Q)") (class "Default")
      (node (ref "IC6") (pin "1") (pinfunction "Q_1") (pintype "output"))
      (node (ref "PH9") (pin "2") (pinfunction "2_2") (pintype "passive"))
    )
    (net (code "141") (name "Net-(IC6A-~{Q})") (class "Default")
      (node (ref "IC6") (pin "2") (pinfunction "~{Q}_2") (pintype "output"))
      (node (ref "PH9") (pin "1") (pinfunction "1_1") (pintype "passive"))
    )
    (net (code "142") (name "Net-(IC6B-CLK)") (class "Default")
      (node (ref "IC6") (pin "13") (pinfunction "CLK_13") (pintype "input"))
      (node (ref "PH25") (pin "2") (pinfunction "2_2") (pintype "passive"))
    )
    (net (code "143") (name "Net-(IC6B-J)") (class "Default")
      (node (ref "IC6") (pin "10") (pinfunction "J_10") (pintype "input"))
      (node (ref "PH25") (pin "3") (pinfunction "3_3") (pintype "passive"))
    )
    (net (code "144") (name "Net-(IC6B-K)") (class "Default")
      (node (ref "IC6") (pin "11") (pinfunction "K_11") (pintype "input"))
      (node (ref "PH25") (pin "1") (pinfunction "1_1") (pintype "passive"))
    )
    (net (code "145") (name "Net-(IC6B-Q)") (class "Default")
      (node (ref "IC6") (pin "15") (pinfunction "Q_15") (pintype "output"))
      (node (ref "PH7") (pin "2") (pinfunction "2_2") (pintype "passive"))
    )
    (net (code "146") (name "Net-(IC6B-~{Q})") (class "Default")
      (node (ref "IC6") (pin "14") (pinfunction "~{Q}_14") (pintype "output"))
      (node (ref "PH7") (pin "1") (pinfunction "1_1") (pintype "passive"))
    )
    (net (code "147") (name "Net-(IC7A-CLK)") (class "Default")
      (node (ref "IC7") (pin "3") (pinfunction "CLK_3") (pintype "input"))
      (node (ref "PH28") (pin "2") (pinfunction "2_2") (pintype "passive"))
    )
    (net (code "148") (name "Net-(IC7A-J)") (class "Default")
      (node (ref "IC7") (pin "6") (pinfunction "J_6") (pintype "input"))
      (node (ref "PH28") (pin "3") (pinfunction "3_3") (pintype "passive"))
    )
    (net (code "149") (name "Net-(IC7A-K)") (class "Default")
      (node (ref "IC7") (pin "5") (pinfunction "K_5") (pintype "input"))
      (node (ref "PH28") (pin "1") (pinfunction "1_1") (pintype "passive"))
    )
    (net (code "150") (name "Net-(IC7A-Q)") (class "Default")
      (node (ref "IC7") (pin "1") (pinfunction "Q_1") (pintype "output"))
      (node (ref "PH10") (pin "2") (pinfunction "2_2") (pintype "passive"))
    )
    (net (code "151") (name "Net-(IC7A-~{Q})") (class "Default")
      (node (ref "IC7") (pin "2") (pinfunction "~{Q}_2") (pintype "output"))
      (node (ref "PH10") (pin "1") (pinfunction "1_1") (pintype "passive"))
    )
    (net (code "152") (name "Net-(IC7B-CLK)") (class "Default")
      (node (ref "IC7") (pin "13") (pinfunction "CLK_13") (pintype "input"))
      (node (ref "PH26") (pin "2") (pinfunction "2_2") (pintype "passive"))
    )
    (net (code "153") (name "Net-(IC7B-J)") (class "Default")
      (node (ref "IC7") (pin "10") (pinfunction "J_10") (pintype "input"))
      (node (ref "PH26") (pin "3") (pinfunction "3_3") (pintype "passive"))
    )
    (net (code "154") (name "Net-(IC7B-K)") (class "Default")
      (node (ref "IC7") (pin "11") (pinfunction "K_11") (pintype "input"))
      (node (ref "PH26") (pin "1") (pinfunction "1_1") (pintype "passive"))
    )
    (net (code "155") (name "Net-(IC7B-Q)") (class "Default")
      (node (ref "IC7") (pin "15") (pinfunction "Q_15") (pintype "output"))
      (node (ref "PH8") (pin "2") (pinfunction "2_2") (pintype "passive"))
    )
    (net (code "156") (name "Net-(IC7B-~{Q})") (class "Default")
      (node (ref "IC7") (pin "14") (pinfunction "~{Q}_14") (pintype "output"))
      (node (ref "PH8") (pin "1") (pinfunction "1_1") (pintype "passive"))
    )
    (net (code "157") (name "Net-(IC8-CV)") (class "Default")
      (node (ref "C21") (pin "1") (pinfunction "1_1") (pintype "passive"))
      (node (ref "IC8") (pin "5") (pinfunction "CV_5") (pintype "input"))
    )
    (net (code "158") (name "Net-(IC8-DIS)") (class "Default")
      (node (ref "IC8") (pin "7") (pinfunction "DIS_7") (pintype "input"))
      (node (ref "PH29") (pin "2") (pinfunction "2_2") (pintype "passive"))
    )
    (net (code "159") (name "Net-(IC8-Q)") (class "Default")
      (node (ref "IC8") (pin "3") (pinfunction "Q_3") (pintype "output"))
      (node (ref "PH1") (pin "1") (pinfunction "1_1") (pintype "passive"))
    )
    (net (code "160") (name "Net-(IC8-THR)") (class "Default")
      (node (ref "IC8") (pin "6") (pinfunction "THR_6") (pintype "input"))
      (node (ref "PH29") (pin "3") (pinfunction "3_3") (pintype "passive"))
    )
    (net (code "161") (name "Net-(IC8-TR)") (class "Default")
      (node (ref "IC8") (pin "2") (pinfunction "TR_2") (pintype "input"))
      (node (ref "PH29") (pin "1") (pinfunction "1_1") (pintype "passive"))
    )
    (net (code "162") (name "Net-(IC9-SNS)") (class "Default")
      (node (ref "C28") (pin "2") (pinfunction "2_2") (pintype "passive"))
      (node (ref "IC9") (pin "4") (pinfunction "SNS_4") (pintype "bidirectional"))
      (node (ref "R40") (pin "2") (pinfunction "2_2") (pintype "passive"))
    )
    (net (code "163") (name "Net-(IC9-SNSK)") (class "Default")
      (node (ref "C28") (pin "1") (pinfunction "1_1") (pintype "passive"))
      (node (ref "IC9") (pin "3") (pinfunction "SNSK_3") (pintype "bidirectional"))
      (node (ref "R67") (pin "2") (pinfunction "2_2") (pintype "passive"))
    )
    (net (code "164") (name "Net-(JC1-Pad1)") (class "Default")
      (node (ref "JC1") (pin "1") (pinfunction "1_1") (pintype "bidirectional"))
      (node (ref "PH12") (pin "3") (pinfunction "3_3") (pintype "passive"))
    )
    (net (code "165") (name "Net-(JC1-Pad2)") (class "Default")
      (node (ref "JC1") (pin "2") (pinfunction "2_2") (pintype "bidirectional"))
      (node (ref "PH12") (pin "2") (pinfunction "2_2") (pintype "passive"))
    )
    (net (code "166") (name "Net-(JC1-Pad3)") (class "Default")
      (node (ref "JC1") (pin "3") (pinfunction "3_3") (pintype "bidirectional"))
      (node (ref "PH12") (pin "1") (pinfunction "1_1") (pintype "passive"))
    )
    (net (code "167") (name "Net-(JMP1-Pad2)") (class "Default")
      (node (ref "JMP1") (pin "2") (pinfunction "2_2") (pintype "passive"))
      (node (ref "R57") (pin "2") (pinfunction "2_2") (pintype "passive"))
    )
    (net (code "168") (name "Net-(JMP2-Pad2)") (class "Default")
      (node (ref "JMP2") (pin "2") (pinfunction "2_2") (pintype "passive"))
      (node (ref "R58") (pin "2") (pinfunction "2_2") (pintype "passive"))
    )
    (net (code "169") (name "Net-(JMP3-Pad2)") (class "Default")
      (node (ref "JMP3") (pin "2") (pinfunction "2_2") (pintype "passive"))
      (node (ref "R59") (pin "2") (pinfunction "2_2") (pintype "passive"))
    )
    (net (code "170") (name "Net-(JMP7-Pad2)") (class "Default")
      (node (ref "JMP7") (pin "2") (pinfunction "2_2") (pintype "passive"))
      (node (ref "PH30") (pin "3") (pinfunction "3_3") (pintype "passive"))
    )
    (net (code "171") (name "Net-(JMP8-Pad2)") (class "Default")
      (node (ref "JMP8") (pin "2") (pinfunction "2_2") (pintype "passive"))
      (node (ref "PH30") (pin "2") (pinfunction "2_2") (pintype "passive"))
    )
    (net (code "172") (name "Net-(JMP9-Pad2)") (class "Default")
      (node (ref "JMP9") (pin "2") (pinfunction "2_2") (pintype "passive"))
      (node (ref "PH30") (pin "1") (pinfunction "1_1") (pintype "passive"))
    )
    (net (code "173") (name "Net-(L0-PadA)") (class "Default")
      (node (ref "L0") (pin "A") (pinfunction "A_A") (pintype "passive"))
      (node (ref "R31") (pin "2") (pinfunction "2_2") (pintype "passive"))
    )
    (net (code "174") (name "Net-(L1-PadA)") (class "Default")
      (node (ref "L1") (pin "A") (pinfunction "A_A") (pintype "passive"))
      (node (ref "R32") (pin "1") (pinfunction "1_1") (pintype "passive"))
    )
    (net (code "175") (name "Net-(L2-PadA)") (class "Default")
      (node (ref "L2") (pin "A") (pinfunction "A_A") (pintype "passive"))
      (node (ref "R33") (pin "1") (pinfunction "1_1") (pintype "passive"))
    )
    (net (code "176") (name "Net-(L3-PadA)") (class "Default")
      (node (ref "L3") (pin "A") (pinfunction "A_A") (pintype "passive"))
      (node (ref "R34") (pin "1") (pinfunction "1_1") (pintype "passive"))
    )
    (net (code "177") (name "Net-(L4-PadA)") (class "Default")
      (node (ref "L4") (pin "A") (pinfunction "A_A") (pintype "passive"))
      (node (ref "R35") (pin "1") (pinfunction "1_1") (pintype "passive"))
    )
    (net (code "178") (name "Net-(L5-PadA)") (class "Default")
      (node (ref "L5") (pin "A") (pinfunction "A_A") (pintype "passive"))
      (node (ref "R36") (pin "1") (pinfunction "1_1") (pintype "passive"))
    )
    (net (code "179") (name "Net-(L6-PadA)") (class "Default")
      (node (ref "L6") (pin "A") (pinfunction "A_A") (pintype "passive"))
      (node (ref "R37") (pin "1") (pinfunction "1_1") (pintype "passive"))
    )
    (net (code "180") (name "Net-(L7-PadA)") (class "Default")
      (node (ref "L7") (pin "A") (pinfunction "A_A") (pintype "passive"))
      (node (ref "R38") (pin "1") (pinfunction "1_1") (pintype "passive"))
    )
    (net (code "181") (name "Net-(L8-PadA)") (class "Default")
      (node (ref "L8") (pin "A") (pinfunction "A_A") (pintype "passive"))
      (node (ref "R48") (pin "1") (pinfunction "1_1") (pintype "passive"))
    )
    (net (code "182") (name "Net-(L9-PadA)") (class "Default")
      (node (ref "L9") (pin "A") (pinfunction "A_A") (pintype "passive"))
      (node (ref "R49") (pin "1") (pinfunction "1_1") (pintype "passive"))
    )
    (net (code "183") (name "Net-(L10-PadA)") (class "Default")
      (node (ref "L10") (pin "A") (pinfunction "A_A") (pintype "passive"))
      (node (ref "R50") (pin "1") (pinfunction "1_1") (pintype "passive"))
    )
    (net (code "184") (name "Net-(L11-PadA)") (class "Default")
      (node (ref "L11") (pin "A") (pinfunction "A_A") (pintype "passive"))
      (node (ref "R51") (pin "1") (pinfunction "1_1") (pintype "passive"))
    )
    (net (code "185") (name "Net-(L12-PadA)") (class "Default")
      (node (ref "L12") (pin "A") (pinfunction "A_A") (pintype "passive"))
      (node (ref "R52") (pin "1") (pinfunction "1_1") (pintype "passive"))
    )
    (net (code "186") (name "Net-(L13-PadA)") (class "Default")
      (node (ref "L13") (pin "A") (pinfunction "A_A") (pintype "passive"))
      (node (ref "R53") (pin "1") (pinfunction "1_1") (pintype "passive"))
    )
    (net (code "187") (name "Net-(L14-PadA)") (class "Default")
      (node (ref "L14") (pin "A") (pinfunction "A_A") (pintype "passive"))
      (node (ref "R54") (pin "1") (pinfunction "1_1") (pintype "passive"))
    )
    (net (code "188") (name "Net-(L15-PadA)") (class "Default")
      (node (ref "L15") (pin "A") (pinfunction "A_A") (pintype "passive"))
      (node (ref "R55") (pin "1") (pinfunction "1_1") (pintype "passive"))
    )
    (net (code "189") (name "Net-(L16-PadA)") (class "Default")
      (node (ref "L16") (pin "A") (pinfunction "A_A") (pintype "passive"))
      (node (ref "R56") (pin "1") (pinfunction "1_1") (pintype "passive"))
    )
    (net (code "190") (name "Net-(LDR-Pad1)") (class "Default")
      (node (ref "LDR") (pin "1") (pinfunction "1_1") (pintype "passive"))
      (node (ref "PH5") (pin "1") (pinfunction "1_1") (pintype "passive"))
    )
    (net (code "191") (name "Net-(LDR-Pad2)") (class "Default")
      (node (ref "LDR") (pin "2") (pinfunction "2_2") (pintype "passive"))
      (node (ref "PH5") (pin "2") (pinfunction "2_2") (pintype "passive"))
    )
    (net (code "192") (name "Net-(MIC-Pad1)") (class "Default")
      (node (ref "MIC") (pin "1") (pinfunction "1_1") (pintype "passive"))
      (node (ref "PH4") (pin "2") (pinfunction "2_2") (pintype "passive"))
    )
    (net (code "193") (name "Net-(MIC-Pad2)") (class "Default")
      (node (ref "MIC") (pin "2") (pinfunction "2_2") (pintype "passive"))
      (node (ref "PH4") (pin "1") (pinfunction "1_1") (pintype "passive"))
    )
    (net (code "194") (name "Net-(NTC-Pad1)") (class "Default")
      (node (ref "NTC") (pin "1") (pinfunction "1_1") (pintype "passive"))
      (node (ref "PH6") (pin "2") (pinfunction "2_2") (pintype "passive"))
    )
    (net (code "195") (name "Net-(NTC-Pad2)") (class "Default")
      (node (ref "NTC") (pin "2") (pinfunction "2_2") (pintype "passive"))
      (node (ref "PH6") (pin "1") (pinfunction "1_1") (pintype "passive"))
    )
    (net (code "196") (name "Net-(P1-Pad1)") (class "Default")
      (node (ref "P1") (pin "1") (pinfunction "1_1") (pintype "passive"))
      (node (ref "PH24") (pin "3") (pinfunction "3_3") (pintype "passive"))
    )
    (net (code "197") (name "Net-(P1-Pad2)") (class "Default")
      (node (ref "P1") (pin "2") (pinfunction "2_2") (pintype "passive"))
      (node (ref "PH24") (pin "2") (pinfunction "2_2") (pintype "passive"))
    )
    (net (code "198") (name "Net-(P1-Pad3)") (class "Default")
      (node (ref "P1") (pin "3") (pinfunction "3_3") (pintype "passive"))
      (node (ref "PH24") (pin "1") (pinfunction "1_1") (pintype "passive"))
    )
    (net (code "199") (name "Net-(P2-Pad1)") (class "Default")
      (node (ref "P2") (pin "1") (pinfunction "1_1") (pintype "passive"))
      (node (ref "PH22") (pin "3") (pinfunction "3_3") (pintype "passive"))
    )
    (net (code "200") (name "Net-(P2-Pad2)") (class "Default")
      (node (ref "P2") (pin "2") (pinfunction "2_2") (pintype "passive"))
      (node (ref "PH22") (pin "2") (pinfunction "2_2") (pintype "passive"))
    )
    (net (code "201") (name "Net-(P2-Pad3)") (class "Default")
      (node (ref "P2") (pin "3") (pinfunction "3_3") (pintype "passive"))
      (node (ref "PH22") (pin "1") (pinfunction "1_1") (pintype "passive"))
    )
    (net (code "202") (name "Net-(P3-Pad1)") (class "Default")
      (node (ref "P3") (pin "1") (pinfunction "1_1") (pintype "passive"))
      (node (ref "PH23") (pin "3") (pinfunction "3_3") (pintype "passive"))
    )
    (net (code "203") (name "Net-(P3-Pad2)") (class "Default")
      (node (ref "P3") (pin "2") (pinfunction "2_2") (pintype "passive"))
      (node (ref "PH23") (pin "2") (pinfunction "2_2") (pintype "passive"))
    )
    (net (code "204") (name "Net-(P3-Pad3)") (class "Default")
      (node (ref "P3") (pin "3") (pinfunction "3_3") (pintype "passive"))
      (node (ref "PH23") (pin "1") (pinfunction "1_1") (pintype "passive"))
    )
    (net (code "205") (name "Net-(PB1-A0)") (class "Default")
      (node (ref "PB1") (pin "1") (pinfunction "A0_1") (pintype "bidirectional"))
      (node (ref "PB1") (pin "2") (pinfunction "A1_2") (pintype "bidirectional"))
      (node (ref "PB2") (pin "1") (pinfunction "A0_1") (pintype "bidirectional"))
      (node (ref "PB2") (pin "2") (pinfunction "A1_2") (pintype "bidirectional"))
      (node (ref "PB3") (pin "1") (pinfunction "A0_1") (pintype "bidirectional"))
      (node (ref "PB3") (pin "2") (pinfunction "A1_2") (pintype "bidirectional"))
      (node (ref "PH19") (pin "3") (pinfunction "3_3") (pintype "passive"))
    )
    (net (code "206") (name "Net-(PB1-B0)") (class "Default")
      (node (ref "PB1") (pin "3") (pinfunction "B0_3") (pintype "bidirectional"))
      (node (ref "PB1") (pin "4") (pinfunction "B1_4") (pintype "bidirectional"))
      (node (ref "PB4") (pin "3") (pinfunction "B0_3") (pintype "bidirectional"))
      (node (ref "PB4") (pin "4") (pinfunction "B1_4") (pintype "bidirectional"))
      (node (ref "PB7") (pin "3") (pinfunction "B0_3") (pintype "bidirectional"))
      (node (ref "PB7") (pin "4") (pinfunction "B1_4") (pintype "bidirectional"))
      (node (ref "PH20") (pin "1") (pinfunction "1_1") (pintype "passive"))
    )
    (net (code "207") (name "Net-(PB2-B0)") (class "Default")
      (node (ref "PB2") (pin "3") (pinfunction "B0_3") (pintype "bidirectional"))
      (node (ref "PB2") (pin "4") (pinfunction "B1_4") (pintype "bidirectional"))
      (node (ref "PB5") (pin "3") (pinfunction "B0_3") (pintype "bidirectional"))
      (node (ref "PB5") (pin "4") (pinfunction "B1_4") (pintype "bidirectional"))
      (node (ref "PB8") (pin "3") (pinfunction "B0_3") (pintype "bidirectional"))
      (node (ref "PB8") (pin "4") (pinfunction "B1_4") (pintype "bidirectional"))
      (node (ref "PH20") (pin "2") (pinfunction "2_2") (pintype "passive"))
    )
    (net (code "208") (name "Net-(PB3-B0)") (class "Default")
      (node (ref "PB3") (pin "3") (pinfunction "B0_3") (pintype "bidirectional"))
      (node (ref "PB3") (pin "4") (pinfunction "B1_4") (pintype "bidirectional"))
      (node (ref "PB6") (pin "3") (pinfunction "B0_3") (pintype "bidirectional"))
      (node (ref "PB6") (pin "4") (pinfunction "B1_4") (pintype "bidirectional"))
      (node (ref "PB9") (pin "3") (pinfunction "B0_3") (pintype "bidirectional"))
      (node (ref "PB9") (pin "4") (pinfunction "B1_4") (pintype "bidirectional"))
      (node (ref "PH20") (pin "3") (pinfunction "3_3") (pintype "passive"))
    )
    (net (code "209") (name "Net-(PB4-A0)") (class "Default")
      (node (ref "PB4") (pin "1") (pinfunction "A0_1") (pintype "bidirectional"))
      (node (ref "PB4") (pin "2") (pinfunction "A1_2") (pintype "bidirectional"))
      (node (ref "PB5") (pin "1") (pinfunction "A0_1") (pintype "bidirectional"))
      (node (ref "PB5") (pin "2") (pinfunction "A1_2") (pintype "bidirectional"))
      (node (ref "PB6") (pin "1") (pinfunction "A0_1") (pintype "bidirectional"))
      (node (ref "PB6") (pin "2") (pinfunction "A1_2") (pintype "bidirectional"))
      (node (ref "PH19") (pin "2") (pinfunction "2_2") (pintype "passive"))
    )
    (net (code "210") (name "Net-(PB7-A0)") (class "Default")
      (node (ref "PB7") (pin "1") (pinfunction "A0_1") (pintype "bidirectional"))
      (node (ref "PB7") (pin "2") (pinfunction "A1_2") (pintype "bidirectional"))
      (node (ref "PB8") (pin "1") (pinfunction "A0_1") (pintype "bidirectional"))
      (node (ref "PB8") (pin "2") (pinfunction "A1_2") (pintype "bidirectional"))
      (node (ref "PB9") (pin "1") (pinfunction "A0_1") (pintype "bidirectional"))
      (node (ref "PB9") (pin "2") (pinfunction "A1_2") (pintype "bidirectional"))
      (node (ref "PH19") (pin "1") (pinfunction "1_1") (pintype "passive"))
    )
    (net (code "211") (name "Net-(PH2-Pad1)") (class "Default")
      (node (ref "PH2") (pin "1") (pinfunction "1_1") (pintype "passive"))
      (node (ref "SP1") (pin "+") (pinfunction "+_+") (pintype "bidirectional"))
    )
    (net (code "212") (name "Net-(PH2-Pad2)") (class "Default")
      (node (ref "PH2") (pin "2") (pinfunction "2_2") (pintype "passive"))
      (node (ref "SP1") (pin "-") (pinfunction "-_-") (pintype "bidirectional"))
    )
    (net (code "213") (name "Net-(PH14-Pad1)") (class "Default")
      (node (ref "PH14") (pin "1") (pinfunction "1_1") (pintype "passive"))
      (node (ref "T4") (pin "C") (pinfunction "C_C") (pintype "passive"))
    )
    (net (code "214") (name "Net-(PH14-Pad2)") (class "Default")
      (node (ref "PH14") (pin "2") (pinfunction "2_2") (pintype "passive"))
      (node (ref "T4") (pin "B") (pinfunction "B_B") (pintype "passive"))
    )
    (net (code "215") (name "Net-(PH14-Pad3)") (class "Default")
      (node (ref "PH14") (pin "3") (pinfunction "3_3") (pintype "passive"))
      (node (ref "T4") (pin "E") (pinfunction "E_E") (pintype "passive"))
    )
    (net (code "216") (name "Net-(PH15-Pad1)") (class "Default")
      (node (ref "PH15") (pin "1") (pinfunction "1_1") (pintype "passive"))
      (node (ref "T5") (pin "C") (pinfunction "C_C") (pintype "passive"))
    )
    (net (code "217") (name "Net-(PH15-Pad2)") (class "Default")
      (node (ref "PH15") (pin "2") (pinfunction "2_2") (pintype "passive"))
      (node (ref "T5") (pin "B") (pinfunction "B_B") (pintype "passive"))
    )
    (net (code "218") (name "Net-(PH15-Pad3)") (class "Default")
      (node (ref "PH15") (pin "3") (pinfunction "3_3") (pintype "passive"))
      (node (ref "T5") (pin "E") (pinfunction "E_E") (pintype "passive"))
    )
    (net (code "219") (name "Net-(PH16-Pad1)") (class "Default")
      (node (ref "PH16") (pin "1") (pinfunction "1_1") (pintype "passive"))
      (node (ref "T1") (pin "E") (pinfunction "E_E") (pintype "passive"))
    )
    (net (code "220") (name "Net-(PH16-Pad2)") (class "Default")
      (node (ref "PH16") (pin "2") (pinfunction "2_2") (pintype "passive"))
      (node (ref "T1") (pin "B") (pinfunction "B_B") (pintype "passive"))
    )
    (net (code "221") (name "Net-(PH16-Pad3)") (class "Default")
      (node (ref "PH16") (pin "3") (pinfunction "3_3") (pintype "passive"))
      (node (ref "T1") (pin "C") (pinfunction "C_C") (pintype "passive"))
    )
    (net (code "222") (name "Net-(PH17-Pad1)") (class "Default")
      (node (ref "PH17") (pin "1") (pinfunction "1_1") (pintype "passive"))
      (node (ref "T2") (pin "E") (pinfunction "E_E") (pintype "passive"))
    )
    (net (code "223") (name "Net-(PH17-Pad2)") (class "Default")
      (node (ref "PH17") (pin "2") (pinfunction "2_2") (pintype "passive"))
      (node (ref "T2") (pin "B") (pinfunction "B_B") (pintype "passive"))
    )
    (net (code "224") (name "Net-(PH17-Pad3)") (class "Default")
      (node (ref "PH17") (pin "3") (pinfunction "3_3") (pintype "passive"))
      (node (ref "T2") (pin "C") (pinfunction "C_C") (pintype "passive"))
    )
    (net (code "225") (name "Net-(PH18-Pad1)") (class "Default")
      (node (ref "PH18") (pin "1") (pinfunction "1_1") (pintype "passive"))
      (node (ref "T3") (pin "E") (pinfunction "E_E") (pintype "passive"))
    )
    (net (code "226") (name "Net-(PH18-Pad2)") (class "Default")
      (node (ref "PH18") (pin "2") (pinfunction "2_2") (pintype "passive"))
      (node (ref "T3") (pin "B") (pinfunction "B_B") (pintype "passive"))
    )
    (net (code "227") (name "Net-(PH18-Pad3)") (class "Default")
      (node (ref "PH18") (pin "3") (pinfunction "3_3") (pintype "passive"))
      (node (ref "T3") (pin "C") (pinfunction "C_C") (pintype "passive"))
    )
    (net (code "228") (name "Net-(PH21-Pad1)") (class "Default")
      (node (ref "PH21") (pin "1") (pinfunction "1_1") (pintype "passive"))
      (node (ref "U$16") (pin "0") (pinfunction "0_0") (pintype "bidirectional"))
    )
    (net (code "229") (name "Net-(PH21-Pad3)") (class "Default")
      (node (ref "PH21") (pin "3") (pinfunction "3_3") (pintype "passive"))
      (node (ref "U$16") (pin "1") (pinfunction "1_1") (pintype "bidirectional"))
    )
    (net (code "230") (name "Net-(PH48-Pad1)") (class "Default")
      (node (ref "PH48") (pin "1") (pinfunction "1_1") (pintype "passive"))
      (node (ref "R28") (pin "1") (pinfunction "1_1") (pintype "passive"))
    )
    (net (code "231") (name "Net-(PH48-Pad2)") (class "Default")
      (node (ref "PH48") (pin "2") (pinfunction "2_2") (pintype "passive"))
      (node (ref "R25") (pin "1") (pinfunction "1_1") (pintype "passive"))
    )
    (net (code "232") (name "Net-(PH48-Pad3)") (class "Default")
      (node (ref "PH48") (pin "3") (pinfunction "3_3") (pintype "passive"))
      (node (ref "R22") (pin "1") (pinfunction "1_1") (pintype "passive"))
    )
    (net (code "233") (name "Net-(PH48-Pad4)") (class "Default")
      (node (ref "PH48") (pin "4") (pinfunction "4_4") (pintype "passive"))
      (node (ref "R19") (pin "1") (pinfunction "1_1") (pintype "passive"))
    )
    (net (code "234") (name "Net-(PH48-Pad5)") (class "Default")
      (node (ref "PH48") (pin "5") (pinfunction "5_5") (pintype "passive"))
      (node (ref "R16") (pin "1") (pinfunction "1_1") (pintype "passive"))
    )
    (net (code "235") (name "Net-(PH48-Pad6)") (class "Default")
      (node (ref "PH48") (pin "6") (pinfunction "6_6") (pintype "passive"))
      (node (ref "R13") (pin "1") (pinfunction "1_1") (pintype "passive"))
    )
    (net (code "236") (name "Net-(PH48-Pad7)") (class "Default")
      (node (ref "PH48") (pin "7") (pinfunction "7_7") (pintype "passive"))
      (node (ref "R10") (pin "1") (pinfunction "1_1") (pintype "passive"))
    )
    (net (code "237") (name "Net-(PH48-Pad8)") (class "Default")
      (node (ref "PH48") (pin "8") (pinfunction "8_8") (pintype "passive"))
      (node (ref "R7") (pin "1") (pinfunction "1_1") (pintype "passive"))
    )
    (net (code "238") (name "Net-(PH48-Pad9)") (class "Default")
      (node (ref "PH48") (pin "9") (pinfunction "9_9") (pintype "passive"))
      (node (ref "R4") (pin "1") (pinfunction "1_1") (pintype "passive"))
    )
    (net (code "239") (name "Net-(PH48-Pad10)") (class "Default")
      (node (ref "PH48") (pin "10") (pinfunction "10_10") (pintype "passive"))
      (node (ref "R1") (pin "1") (pinfunction "1_1") (pintype "passive"))
    )
    (net (code "240") (name "Net-(PH49-Pad1)") (class "Default")
      (node (ref "PH49") (pin "1") (pinfunction "1_1") (pintype "passive"))
      (node (ref "R1") (pin "2") (pinfunction "2_2") (pintype "passive"))
    )
    (net (code "241") (name "Net-(PH49-Pad2)") (class "Default")
      (node (ref "PH49") (pin "2") (pinfunction "2_2") (pintype "passive"))
      (node (ref "R4") (pin "2") (pinfunction "2_2") (pintype "passive"))
    )
    (net (code "242") (name "Net-(PH49-Pad3)") (class "Default")
      (node (ref "PH49") (pin "3") (pinfunction "3_3") (pintype "passive"))
      (node (ref "R7") (pin "2") (pinfunction "2_2") (pintype "passive"))
    )
    (net (code "243") (name "Net-(PH49-Pad4)") (class "Default")
      (node (ref "PH49") (pin "4") (pinfunction "4_4") (pintype "passive"))
      (node (ref "R10") (pin "2") (pinfunction "2_2") (pintype "passive"))
    )
    (net (code "244") (name "Net-(PH49-Pad5)") (class "Default")
      (node (ref "PH49") (pin "5") (pinfunction "5_5") (pintype "passive"))
      (node (ref "R13") (pin "2") (pinfunction "2_2") (pintype "passive"))
    )
    (net (code "245") (name "Net-(PH49-Pad6)") (class "Default")
      (node (ref "PH49") (pin "6") (pinfunction "6_6") (pintype "passive"))
      (node (ref "R16") (pin "2") (pinfunction "2_2") (pintype "passive"))
    )
    (net (code "246") (name "Net-(PH49-Pad7)") (class "Default")
      (node (ref "PH49") (pin "7") (pinfunction "7_7") (pintype "passive"))
      (node (ref "R19") (pin "2") (pinfunction "2_2") (pintype "passive"))
    )
    (net (code "247") (name "Net-(PH49-Pad8)") (class "Default")
      (node (ref "PH49") (pin "8") (pinfunction "8_8") (pintype "passive"))
      (node (ref "R22") (pin "2") (pinfunction "2_2") (pintype "passive"))
    )
    (net (code "248") (name "Net-(PH49-Pad9)") (class "Default")
      (node (ref "PH49") (pin "9") (pinfunction "9_9") (pintype "passive"))
      (node (ref "R25") (pin "2") (pinfunction "2_2") (pintype "passive"))
    )
    (net (code "249") (name "Net-(PH49-Pad10)") (class "Default")
      (node (ref "PH49") (pin "10") (pinfunction "10_10") (pintype "passive"))
      (node (ref "R28") (pin "2") (pinfunction "2_2") (pintype "passive"))
    )
    (net (code "250") (name "Net-(PH50-Pad1)") (class "Default")
      (node (ref "PH50") (pin "1") (pinfunction "1_1") (pintype "passive"))
      (node (ref "R29") (pin "1") (pinfunction "1_1") (pintype "passive"))
    )
    (net (code "251") (name "Net-(PH50-Pad2)") (class "Default")
      (node (ref "PH50") (pin "2") (pinfunction "2_2") (pintype "passive"))
      (node (ref "R26") (pin "1") (pinfunction "1_1") (pintype "passive"))
    )
    (net (code "252") (name "Net-(PH50-Pad3)") (class "Default")
      (node (ref "PH50") (pin "3") (pinfunction "3_3") (pintype "passive"))
      (node (ref "R23") (pin "1") (pinfunction "1_1") (pintype "passive"))
    )
    (net (code "253") (name "Net-(PH50-Pad4)") (class "Default")
      (node (ref "PH50") (pin "4") (pinfunction "4_4") (pintype "passive"))
      (node (ref "R20") (pin "1") (pinfunction "1_1") (pintype "passive"))
    )
    (net (code "254") (name "Net-(PH50-Pad5)") (class "Default")
      (node (ref "PH50") (pin "5") (pinfunction "5_5") (pintype "passive"))
      (node (ref "R17") (pin "1") (pinfunction "1_1") (pintype "passive"))
    )
    (net (code "255") (name "Net-(PH50-Pad6)") (class "Default")
      (node (ref "PH50") (pin "6") (pinfunction "6_6") (pintype "passive"))
      (node (ref "R14") (pin "1") (pinfunction "1_1") (pintype "passive"))
    )
    (net (code "256") (name "Net-(PH50-Pad7)") (class "Default")
      (node (ref "PH50") (pin "7") (pinfunction "7_7") (pintype "passive"))
      (node (ref "R11") (pin "1") (pinfunction "1_1") (pintype "passive"))
    )
    (net (code "257") (name "Net-(PH50-Pad8)") (class "Default")
      (node (ref "PH50") (pin "8") (pinfunction "8_8") (pintype "passive"))
      (node (ref "R8") (pin "1") (pinfunction "1_1") (pintype "passive"))
    )
    (net (code "258") (name "Net-(PH50-Pad9)") (class "Default")
      (node (ref "PH50") (pin "9") (pinfunction "9_9") (pintype "passive"))
      (node (ref "R5") (pin "1") (pinfunction "1_1") (pintype "passive"))
    )
    (net (code "259") (name "Net-(PH50-Pad10)") (class "Default")
      (node (ref "PH50") (pin "10") (pinfunction "10_10") (pintype "passive"))
      (node (ref "R2") (pin "1") (pinfunction "1_1") (pintype "passive"))
    )
    (net (code "260") (name "Net-(PH51-Pad1)") (class "Default")
      (node (ref "PH51") (pin "1") (pinfunction "1_1") (pintype "passive"))
      (node (ref "R2") (pin "2") (pinfunction "2_2") (pintype "passive"))
    )
    (net (code "261") (name "Net-(PH51-Pad2)") (class "Default")
      (node (ref "PH51") (pin "2") (pinfunction "2_2") (pintype "passive"))
      (node (ref "R5") (pin "2") (pinfunction "2_2") (pintype "passive"))
    )
    (net (code "262") (name "Net-(PH51-Pad3)") (class "Default")
      (node (ref "PH51") (pin "3") (pinfunction "3_3") (pintype "passive"))
      (node (ref "R8") (pin "2") (pinfunction "2_2") (pintype "passive"))
    )
    (net (code "263") (name "Net-(PH51-Pad4)") (class "Default")
      (node (ref "PH51") (pin "4") (pinfunction "4_4") (pintype "passive"))
      (node (ref "R11") (pin "2") (pinfunction "2_2") (pintype "passive"))
    )
    (net (code "264") (name "Net-(PH51-Pad5)") (class "Default")
      (node (ref "PH51") (pin "5") (pinfunction "5_5") (pintype "passive"))
      (node (ref "R14") (pin "2") (pinfunction "2_2") (pintype "passive"))
    )
    (net (code "265") (name "Net-(PH51-Pad6)") (class "Default")
      (node (ref "PH51") (pin "6") (pinfunction "6_6") (pintype "passive"))
      (node (ref "R17") (pin "2") (pinfunction "2_2") (pintype "passive"))
    )
    (net (code "266") (name "Net-(PH51-Pad7)") (class "Default")
      (node (ref "PH51") (pin "7") (pinfunction "7_7") (pintype "passive"))
      (node (ref "R20") (pin "2") (pinfunction "2_2") (pintype "passive"))
    )
    (net (code "267") (name "Net-(PH51-Pad8)") (class "Default")
      (node (ref "PH51") (pin "8") (pinfunction "8_8") (pintype "passive"))
      (node (ref "R23") (pin "2") (pinfunction "2_2") (pintype "passive"))
    )
    (net (code "268") (name "Net-(PH51-Pad9)") (class "Default")
      (node (ref "PH51") (pin "9") (pinfunction "9_9") (pintype "passive"))
      (node (ref "R26") (pin "2") (pinfunction "2_2") (pintype "passive"))
    )
    (net (code "269") (name "Net-(PH51-Pad10)") (class "Default")
      (node (ref "PH51") (pin "10") (pinfunction "10_10") (pintype "passive"))
      (node (ref "R29") (pin "2") (pinfunction "2_2") (pintype "passive"))
    )
    (net (code "270") (name "Net-(PH52-Pad1)") (class "Default")
      (node (ref "PH52") (pin "1") (pinfunction "1_1") (pintype "passive"))
      (node (ref "R30") (pin "1") (pinfunction "1_1") (pintype "passive"))
    )
    (net (code "271") (name "Net-(PH52-Pad2)") (class "Default")
      (node (ref "PH52") (pin "2") (pinfunction "2_2") (pintype "passive"))
      (node (ref "R27") (pin "1") (pinfunction "1_1") (pintype "passive"))
    )
    (net (code "272") (name "Net-(PH52-Pad3)") (class "Default")
      (node (ref "PH52") (pin "3") (pinfunction "3_3") (pintype "passive"))
      (node (ref "R24") (pin "1") (pinfunction "1_1") (pintype "passive"))
    )
    (net (code "273") (name "Net-(PH52-Pad4)") (class "Default")
      (node (ref "PH52") (pin "4") (pinfunction "4_4") (pintype "passive"))
      (node (ref "R21") (pin "1") (pinfunction "1_1") (pintype "passive"))
    )
    (net (code "274") (name "Net-(PH52-Pad5)") (class "Default")
      (node (ref "PH52") (pin "5") (pinfunction "5_5") (pintype "passive"))
      (node (ref "R18") (pin "1") (pinfunction "1_1") (pintype "passive"))
    )
    (net (code "275") (name "Net-(PH52-Pad6)") (class "Default")
      (node (ref "PH52") (pin "6") (pinfunction "6_6") (pintype "passive"))
      (node (ref "R15") (pin "1") (pinfunction "1_1") (pintype "passive"))
    )
    (net (code "276") (name "Net-(PH52-Pad7)") (class "Default")
      (node (ref "PH52") (pin "7") (pinfunction "7_7") (pintype "passive"))
      (node (ref "R12") (pin "1") (pinfunction "1_1") (pintype "passive"))
    )
    (net (code "277") (name "Net-(PH52-Pad8)") (class "Default")
      (node (ref "PH52") (pin "8") (pinfunction "8_8") (pintype "passive"))
      (node (ref "R9") (pin "1") (pinfunction "1_1") (pintype "passive"))
    )
    (net (code "278") (name "Net-(PH52-Pad9)") (class "Default")
      (node (ref "PH52") (pin "9") (pinfunction "9_9") (pintype "passive"))
      (node (ref "R6") (pin "1") (pinfunction "1_1") (pintype "passive"))
    )
    (net (code "279") (name "Net-(PH52-Pad10)") (class "Default")
      (node (ref "PH52") (pin "10") (pinfunction "10_10") (pintype "passive"))
      (node (ref "R3") (pin "1") (pinfunction "1_1") (pintype "passive"))
    )
    (net (code "280") (name "Net-(PH53-Pad1)") (class "Default")
      (node (ref "PH53") (pin "1") (pinfunction "1_1") (pintype "passive"))
      (node (ref "R3") (pin "2") (pinfunction "2_2") (pintype "passive"))
    )
    (net (code "281") (name "Net-(PH53-Pad2)") (class "Default")
      (node (ref "PH53") (pin "2") (pinfunction "2_2") (pintype "passive"))
      (node (ref "R6") (pin "2") (pinfunction "2_2") (pintype "passive"))
    )
    (net (code "282") (name "Net-(PH53-Pad3)") (class "Default")
      (node (ref "PH53") (pin "3") (pinfunction "3_3") (pintype "passive"))
      (node (ref "R9") (pin "2") (pinfunction "2_2") (pintype "passive"))
    )
    (net (code "283") (name "Net-(PH53-Pad4)") (class "Default")
      (node (ref "PH53") (pin "4") (pinfunction "4_4") (pintype "passive"))
      (node (ref "R12") (pin "2") (pinfunction "2_2") (pintype "passive"))
    )
    (net (code "284") (name "Net-(PH53-Pad5)") (class "Default")
      (node (ref "PH53") (pin "5") (pinfunction "5_5") (pintype "passive"))
      (node (ref "R15") (pin "2") (pinfunction "2_2") (pintype "passive"))
    )
    (net (code "285") (name "Net-(PH53-Pad6)") (class "Default")
      (node (ref "PH53") (pin "6") (pinfunction "6_6") (pintype "passive"))
      (node (ref "R18") (pin "2") (pinfunction "2_2") (pintype "passive"))
    )
    (net (code "286") (name "Net-(PH53-Pad7)") (class "Default")
      (node (ref "PH53") (pin "7") (pinfunction "7_7") (pintype "passive"))
      (node (ref "R21") (pin "2") (pinfunction "2_2") (pintype "passive"))
    )
    (net (code "287") (name "Net-(PH53-Pad8)") (class "Default")
      (node (ref "PH53") (pin "8") (pinfunction "8_8") (pintype "passive"))
      (node (ref "R24") (pin "2") (pinfunction "2_2") (pintype "passive"))
    )
    (net (code "288") (name "Net-(PH53-Pad9)") (class "Default")
      (node (ref "PH53") (pin "9") (pinfunction "9_9") (pintype "passive"))
      (node (ref "R27") (pin "2") (pinfunction "2_2") (pintype "passive"))
    )
    (net (code "289") (name "Net-(PH53-Pad10)") (class "Default")
      (node (ref "PH53") (pin "10") (pinfunction "10_10") (pintype "passive"))
      (node (ref "R30") (pin "2") (pinfunction "2_2") (pintype "passive"))
    )
    (net (code "290") (name "Net-(PH59-Pad1)") (class "Default")
      (node (ref "PH59") (pin "1") (pinfunction "1_1") (pintype "passive"))
      (node (ref "PH60") (pin "1") (pinfunction "1_1") (pintype "passive"))
      (node (ref "PH61") (pin "1") (pinfunction "1_1") (pintype "passive"))
    )
    (net (code "291") (name "Net-(PH59-Pad2)") (class "Default")
      (node (ref "PH59") (pin "2") (pinfunction "2_2") (pintype "passive"))
      (node (ref "PH60") (pin "2") (pinfunction "2_2") (pintype "passive"))
      (node (ref "PH61") (pin "2") (pinfunction "2_2") (pintype "passive"))
    )
    (net (code "292") (name "Net-(PH59-Pad3)") (class "Default")
      (node (ref "PH59") (pin "3") (pinfunction "3_3") (pintype "passive"))
      (node (ref "PH60") (pin "3") (pinfunction "3_3") (pintype "passive"))
      (node (ref "PH61") (pin "3") (pinfunction "3_3") (pintype "passive"))
    )
    (net (code "293") (name "Net-(PH59-Pad4)") (class "Default")
      (node (ref "PH59") (pin "4") (pinfunction "4_4") (pintype "passive"))
      (node (ref "PH60") (pin "4") (pinfunction "4_4") (pintype "passive"))
      (node (ref "PH61") (pin "4") (pinfunction "4_4") (pintype "passive"))
    )
    (net (code "294") (name "Net-(PH59-Pad5)") (class "Default")
      (node (ref "PH59") (pin "5") (pinfunction "5_5") (pintype "passive"))
      (node (ref "PH60") (pin "5") (pinfunction "5_5") (pintype "passive"))
      (node (ref "PH61") (pin "5") (pinfunction "5_5") (pintype "passive"))
    )
    (net (code "295") (name "Net-(PH59-Pad6)") (class "Default")
      (node (ref "PH59") (pin "6") (pinfunction "6_6") (pintype "passive"))
      (node (ref "PH60") (pin "6") (pinfunction "6_6") (pintype "passive"))
      (node (ref "PH61") (pin "6") (pinfunction "6_6") (pintype "passive"))
    )
    (net (code "296") (name "Net-(PH59-Pad7)") (class "Default")
      (node (ref "PH59") (pin "7") (pinfunction "7_7") (pintype "passive"))
      (node (ref "PH60") (pin "7") (pinfunction "7_7") (pintype "passive"))
      (node (ref "PH61") (pin "7") (pinfunction "7_7") (pintype "passive"))
    )
    (net (code "297") (name "Net-(PH59-Pad8)") (class "Default")
      (node (ref "PH59") (pin "8") (pinfunction "8_8") (pintype "passive"))
      (node (ref "PH60") (pin "8") (pinfunction "8_8") (pintype "passive"))
      (node (ref "PH61") (pin "8") (pinfunction "8_8") (pintype "passive"))
    )
    (net (code "298") (name "Net-(PH59-Pad9)") (class "Default")
      (node (ref "PH59") (pin "9") (pinfunction "9_9") (pintype "passive"))
      (node (ref "PH60") (pin "9") (pinfunction "9_9") (pintype "passive"))
      (node (ref "PH61") (pin "9") (pinfunction "9_9") (pintype "passive"))
    )
    (net (code "299") (name "Net-(PH59-Pad10)") (class "Default")
      (node (ref "PH59") (pin "10") (pinfunction "10_10") (pintype "passive"))
      (node (ref "PH60") (pin "10") (pinfunction "10_10") (pintype "passive"))
      (node (ref "PH61") (pin "10") (pinfunction "10_10") (pintype "passive"))
    )
    (net (code "300") (name "Net-(PH59-Pad11)") (class "Default")
      (node (ref "PH59") (pin "11") (pinfunction "11_11") (pintype "passive"))
      (node (ref "PH60") (pin "11") (pinfunction "11_11") (pintype "passive"))
      (node (ref "PH61") (pin "11") (pinfunction "11_11") (pintype "passive"))
    )
    (net (code "301") (name "Net-(PH59-Pad12)") (class "Default")
      (node (ref "PH59") (pin "12") (pinfunction "12_12") (pintype "passive"))
      (node (ref "PH60") (pin "12") (pinfunction "12_12") (pintype "passive"))
      (node (ref "PH61") (pin "12") (pinfunction "12_12") (pintype "passive"))
    )
    (net (code "302") (name "Net-(PH59-Pad13)") (class "Default")
      (node (ref "PH59") (pin "13") (pinfunction "13_13") (pintype "passive"))
      (node (ref "PH60") (pin "13") (pinfunction "13_13") (pintype "passive"))
      (node (ref "PH61") (pin "13") (pinfunction "13_13") (pintype "passive"))
    )
    (net (code "303") (name "Net-(PH59-Pad14)") (class "Default")
      (node (ref "PH59") (pin "14") (pinfunction "14_14") (pintype "passive"))
      (node (ref "PH60") (pin "14") (pinfunction "14_14") (pintype "passive"))
      (node (ref "PH61") (pin "14") (pinfunction "14_14") (pintype "passive"))
    )
    (net (code "304") (name "Net-(PH59-Pad15)") (class "Default")
      (node (ref "PH59") (pin "15") (pinfunction "15_15") (pintype "passive"))
      (node (ref "PH60") (pin "15") (pinfunction "15_15") (pintype "passive"))
      (node (ref "PH61") (pin "15") (pinfunction "15_15") (pintype "passive"))
    )
    (net (code "305") (name "Net-(PH59-Pad16)") (class "Default")
      (node (ref "PH59") (pin "16") (pinfunction "16_16") (pintype "passive"))
      (node (ref "PH60") (pin "16") (pinfunction "16_16") (pintype "passive"))
      (node (ref "PH61") (pin "16") (pinfunction "16_16") (pintype "passive"))
    )
    (net (code "306") (name "Net-(PH59-Pad17)") (class "Default")
      (node (ref "PH59") (pin "17") (pinfunction "17_17") (pintype "passive"))
      (node (ref "PH60") (pin "17") (pinfunction "17_17") (pintype "passive"))
      (node (ref "PH61") (pin "17") (pinfunction "17_17") (pintype "passive"))
    )
    (net (code "307") (name "Net-(PH59-Pad18)") (class "Default")
      (node (ref "PH59") (pin "18") (pinfunction "18_18") (pintype "passive"))
      (node (ref "PH60") (pin "18") (pinfunction "18_18") (pintype "passive"))
      (node (ref "PH61") (pin "18") (pinfunction "18_18") (pintype "passive"))
    )
    (net (code "308") (name "Net-(PH59-Pad19)") (class "Default")
      (node (ref "PH59") (pin "19") (pinfunction "19_19") (pintype "passive"))
      (node (ref "PH60") (pin "19") (pinfunction "19_19") (pintype "passive"))
      (node (ref "PH61") (pin "19") (pinfunction "19_19") (pintype "passive"))
    )
    (net (code "309") (name "Net-(PH59-Pad20)") (class "Default")
      (node (ref "PH59") (pin "20") (pinfunction "20_20") (pintype "passive"))
      (node (ref "PH60") (pin "20") (pinfunction "20_20") (pintype "passive"))
      (node (ref "PH61") (pin "20") (pinfunction "20_20") (pintype "passive"))
    )
    (net (code "310") (name "Net-(PH59-Pad21)") (class "Default")
      (node (ref "PH59") (pin "21") (pinfunction "21_21") (pintype "passive"))
      (node (ref "PH60") (pin "21") (pinfunction "21_21") (pintype "passive"))
      (node (ref "PH61") (pin "21") (pinfunction "21_21") (pintype "passive"))
    )
    (net (code "311") (name "Net-(PH59-Pad22)") (class "Default")
      (node (ref "PH59") (pin "22") (pinfunction "22_22") (pintype "passive"))
      (node (ref "PH60") (pin "22") (pinfunction "22_22") (pintype "passive"))
      (node (ref "PH61") (pin "22") (pinfunction "22_22") (pintype "passive"))
    )
    (net (code "312") (name "Net-(PH59-Pad23)") (class "Default")
      (node (ref "PH59") (pin "23") (pinfunction "23_23") (pintype "passive"))
      (node (ref "PH60") (pin "23") (pinfunction "23_23") (pintype "passive"))
      (node (ref "PH61") (pin "23") (pinfunction "23_23") (pintype "passive"))
    )
    (net (code "313") (name "Net-(PH59-Pad24)") (class "Default")
      (node (ref "PH59") (pin "24") (pinfunction "24_24") (pintype "passive"))
      (node (ref "PH60") (pin "24") (pinfunction "24_24") (pintype "passive"))
      (node (ref "PH61") (pin "24") (pinfunction "24_24") (pintype "passive"))
    )
    (net (code "314") (name "Net-(PH59-Pad25)") (class "Default")
      (node (ref "PH59") (pin "25") (pinfunction "25_25") (pintype "passive"))
      (node (ref "PH60") (pin "25") (pinfunction "25_25") (pintype "passive"))
      (node (ref "PH61") (pin "25") (pinfunction "25_25") (pintype "passive"))
    )
    (net (code "315") (name "Net-(PH59-Pad26)") (class "Default")
      (node (ref "PH59") (pin "26") (pinfunction "26_26") (pintype "passive"))
      (node (ref "PH60") (pin "26") (pinfunction "26_26") (pintype "passive"))
      (node (ref "PH61") (pin "26") (pinfunction "26_26") (pintype "passive"))
    )
    (net (code "316") (name "Net-(PH59-Pad27)") (class "Default")
      (node (ref "PH59") (pin "27") (pinfunction "27_27") (pintype "passive"))
      (node (ref "PH60") (pin "27") (pinfunction "27_27") (pintype "passive"))
      (node (ref "PH61") (pin "27") (pinfunction "27_27") (pintype "passive"))
    )
    (net (code "317") (name "Net-(PH59-Pad28)") (class "Default")
      (node (ref "PH59") (pin "28") (pinfunction "28_28") (pintype "passive"))
      (node (ref "PH60") (pin "28") (pinfunction "28_28") (pintype "passive"))
      (node (ref "PH61") (pin "28") (pinfunction "28_28") (pintype "passive"))
    )
    (net (code "318") (name "Net-(PH59-Pad29)") (class "Default")
      (node (ref "PH59") (pin "29") (pinfunction "29_29") (pintype "passive"))
      (node (ref "PH60") (pin "29") (pinfunction "29_29") (pintype "passive"))
      (node (ref "PH61") (pin "29") (pinfunction "29_29") (pintype "passive"))
    )
    (net (code "319") (name "Net-(PH59-Pad30)") (class "Default")
      (node (ref "PH59") (pin "30") (pinfunction "30_30") (pintype "passive"))
      (node (ref "PH60") (pin "30") (pinfunction "30_30") (pintype "passive"))
      (node (ref "PH61") (pin "30") (pinfunction "30_30") (pintype "passive"))
    )
    (net (code "320") (name "Net-(RGBA-A)") (class "Default")
      (node (ref "R57") (pin "1") (pinfunction "1_1") (pintype "passive"))
      (node (ref "RGB") (pin "1") (pinfunction "A_1") (pintype "passive"))
    )
    (net (code "321") (name "Net-(RGBA-C)") (class "Default")
      (node (ref "JMP4") (pin "2") (pinfunction "2_2") (pintype "passive"))
      (node (ref "RGB") (pin "2") (pinfunction "C_2") (pintype "passive"))
    )
    (net (code "322") (name "Net-(RGBB-A)") (class "Default")
      (node (ref "R59") (pin "1") (pinfunction "1_1") (pintype "passive"))
      (node (ref "RGB") (pin "5") (pinfunction "A_5") (pintype "passive"))
    )
    (net (code "323") (name "Net-(RGBB-C)") (class "Default")
      (node (ref "JMP6") (pin "2") (pinfunction "2_2") (pintype "passive"))
      (node (ref "RGB") (pin "6") (pinfunction "C_6") (pintype "passive"))
    )
    (net (code "324") (name "Net-(RGBC-A)") (class "Default")
      (node (ref "R58") (pin "1") (pinfunction "1_1") (pintype "passive"))
      (node (ref "RGB") (pin "3") (pinfunction "A_3") (pintype "passive"))
    )
    (net (code "325") (name "Net-(RGBC-C)") (class "Default")
      (node (ref "JMP5") (pin "2") (pinfunction "2_2") (pintype "passive"))
      (node (ref "RGB") (pin "4") (pinfunction "C_4") (pintype "passive"))
    )
    (net (code "326") (name "O1A") (class "Default")
      (node (ref "AR2") (pin "9") (pinfunction "9_9") (pintype "bidirectional"))
      (node (ref "IC4") (pin "1") (pinfunction "1A_1") (pintype "input"))
      (node (ref "PH46") (pin "1") (pinfunction "1_1") (pintype "passive"))
    )
    (net (code "327") (name "O1B") (class "Default")
      (node (ref "AR2") (pin "8") (pinfunction "8_8") (pintype "bidirectional"))
      (node (ref "IC4") (pin "2") (pinfunction "1B_2") (pintype "input"))
      (node (ref "PH46") (pin "2") (pinfunction "2_2") (pintype "passive"))
    )
    (net (code "328") (name "O1Y") (class "Default")
      (node (ref "IC4") (pin "3") (pinfunction "1Y_3") (pintype "output"))
      (node (ref "PH37") (pin "1") (pinfunction "1_1") (pintype "passive"))
    )
    (net (code "329") (name "O2A") (class "Default")
      (node (ref "AR2") (pin "7") (pinfunction "7_7") (pintype "bidirectional"))
      (node (ref "IC4") (pin "4") (pinfunction "2A_4") (pintype "input"))
      (node (ref "PH46") (pin "3") (pinfunction "3_3") (pintype "passive"))
    )
    (net (code "330") (name "O2B") (class "Default")
      (node (ref "AR2") (pin "6") (pinfunction "6_6") (pintype "bidirectional"))
      (node (ref "IC4") (pin "5") (pinfunction "2B_5") (pintype "input"))
      (node (ref "PH46") (pin "4") (pinfunction "4_4") (pintype "passive"))
    )
    (net (code "331") (name "O2Y") (class "Default")
      (node (ref "IC4") (pin "6") (pinfunction "2Y_6") (pintype "output"))
      (node (ref "PH37") (pin "2") (pinfunction "2_2") (pintype "passive"))
    )
    (net (code "332") (name "O3A") (class "Default")
      (node (ref "AR2") (pin "1") (pinfunction "1_1") (pintype "bidirectional"))
      (node (ref "IC4") (pin "9") (pinfunction "3A_9") (pintype "input"))
      (node (ref "PH46") (pin "5") (pinfunction "5_5") (pintype "passive"))
    )
    (net (code "333") (name "O3B") (class "Default")
      (node (ref "AR2") (pin "2") (pinfunction "2_2") (pintype "bidirectional"))
      (node (ref "IC4") (pin "10") (pinfunction "3B_10") (pintype "input"))
      (node (ref "PH46") (pin "6") (pinfunction "6_6") (pintype "passive"))
    )
    (net (code "334") (name "O3Y") (class "Default")
      (node (ref "IC4") (pin "8") (pinfunction "3Y_8") (pintype "output"))
      (node (ref "PH37") (pin "3") (pinfunction "3_3") (pintype "passive"))
    )
    (net (code "335") (name "O4A") (class "Default")
      (node (ref "AR2") (pin "3") (pinfunction "3_3") (pintype "bidirectional"))
      (node (ref "IC4") (pin "12") (pinfunction "4A_12") (pintype "input"))
      (node (ref "PH46") (pin "7") (pinfunction "7_7") (pintype "passive"))
    )
    (net (code "336") (name "O4B") (class "Default")
      (node (ref "AR2") (pin "4") (pinfunction "4_4") (pintype "bidirectional"))
      (node (ref "IC4") (pin "13") (pinfunction "4B_13") (pintype "input"))
      (node (ref "PH46") (pin "8") (pinfunction "8_8") (pintype "passive"))
    )
    (net (code "337") (name "O4Y") (class "Default")
      (node (ref "IC4") (pin "11") (pinfunction "4Y_11") (pintype "output"))
      (node (ref "PH37") (pin "4") (pinfunction "4_4") (pintype "passive"))
    )
    (net (code "338") (name "OUT01") (class "Default")
      (node (ref "IC9") (pin "1") (pinfunction "OUT_1") (pintype "bidirectional"))
      (node (ref "PH21") (pin "2") (pinfunction "2_2") (pintype "passive"))
      (node (ref "R39") (pin "2") (pinfunction "2_2") (pintype "passive"))
    )
    (net (code "339") (name "PVDD") (class "Default")
      (node (ref "C23") (pin "1") (pinfunction "1_1") (pintype "passive"))
      (node (ref "C24") (pin "1") (pinfunction "1_1") (pintype "passive"))
      (node (ref "C27") (pin "+") (pinfunction "+_+") (pintype "passive"))
      (node (ref "IC11") (pin "13") (pinfunction "PVDD1_13") (pintype "output"))
      (node (ref "IC11") (pin "4") (pinfunction "PVDD_4") (pintype "input"))
      (node (ref "IC11") (pin "6") (pinfunction "VDD_6") (pintype "input"))
      (node (ref "PH38") (pin "3") (pinfunction "3_3") (pintype "passive"))
    )
    (net (code "340") (name "R") (class "Default")
      (node (ref "JMP2") (pin "1") (pinfunction "1_1") (pintype "passive"))
      (node (ref "JMP6") (pin "1") (pinfunction "1_1") (pintype "passive"))
      (node (ref "PH11") (pin "1") (pinfunction "1_1") (pintype "passive"))
    )
    (net (code "341") (name "SA") (class "Default")
      (node (ref "DP1") (pin "10") (pinfunction "10_10") (pintype "bidirectional"))
      (node (ref "R41") (pin "2") (pinfunction "2_2") (pintype "passive"))
    )
    (net (code "342") (name "SA'") (class "Default")
      (node (ref "IC10") (pin "A") (pinfunction "A_A") (pintype "bidirectional"))
      (node (ref "PH31") (pin "1") (pinfunction "1_1") (pintype "passive"))
      (node (ref "R41") (pin "1") (pinfunction "1_1") (pintype "passive"))
    )
    (net (code "343") (name "SB") (class "Default")
      (node (ref "DP1") (pin "8") (pinfunction "8_8") (pintype "bidirectional"))
      (node (ref "R42") (pin "2") (pinfunction "2_2") (pintype "passive"))
    )
    (net (code "344") (name "SB'") (class "Default")
      (node (ref "IC10") (pin "B") (pinfunction "B_B") (pintype "bidirectional"))
      (node (ref "PH13") (pin "1") (pinfunction "1_1") (pintype "passive"))
      (node (ref "R42") (pin "1") (pinfunction "1_1") (pintype "passive"))
    )
    (net (code "345") (name "SC") (class "Default")
      (node (ref "DP1") (pin "1") (pinfunction "1_1") (pintype "bidirectional"))
      (node (ref "R43") (pin "2") (pinfunction "2_2") (pintype "passive"))
    )
    (net (code "346") (name "SC'") (class "Default")
      (node (ref "IC10") (pin "C") (pinfunction "C_C") (pintype "bidirectional"))
      (node (ref "PH13") (pin "3") (pinfunction "3_3") (pintype "passive"))
      (node (ref "R43") (pin "1") (pinfunction "1_1") (pintype "passive"))
    )
    (net (code "347") (name "SD") (class "Default")
      (node (ref "DP1") (pin "5") (pinfunction "5_5") (pintype "bidirectional"))
      (node (ref "R44") (pin "2") (pinfunction "2_2") (pintype "passive"))
    )
    (net (code "348") (name "SD'") (class "Default")
      (node (ref "IC10") (pin "D") (pinfunction "D_D") (pintype "bidirectional"))
      (node (ref "PH31") (pin "4") (pinfunction "4_4") (pintype "passive"))
      (node (ref "R44") (pin "1") (pinfunction "1_1") (pintype "passive"))
    )
    (net (code "349") (name "SE") (class "Default")
      (node (ref "DP1") (pin "3") (pinfunction "3_3") (pintype "bidirectional"))
      (node (ref "R45") (pin "2") (pinfunction "2_2") (pintype "passive"))
    )
    (net (code "350") (name "SE'") (class "Default")
      (node (ref "IC10") (pin "E") (pinfunction "E_E") (pintype "bidirectional"))
      (node (ref "PH31") (pin "3") (pinfunction "3_3") (pintype "passive"))
      (node (ref "R45") (pin "1") (pinfunction "1_1") (pintype "passive"))
    )
    (net (code "351") (name "SENSE") (class "Default")
      (node (ref "R67") (pin "1") (pinfunction "1_1") (pintype "passive"))
      (node (ref "U$15") (pin "0") (pinfunction "0_0") (pintype "bidirectional"))
    )
    (net (code "352") (name "SF") (class "Default")
      (node (ref "DP1") (pin "6") (pinfunction "6_6") (pintype "bidirectional"))
      (node (ref "R46") (pin "2") (pinfunction "2_2") (pintype "passive"))
    )
    (net (code "353") (name "SF'") (class "Default")
      (node (ref "IC10") (pin "F") (pinfunction "F_F") (pintype "bidirectional"))
      (node (ref "PH31") (pin "2") (pinfunction "2_2") (pintype "passive"))
      (node (ref "R46") (pin "1") (pinfunction "1_1") (pintype "passive"))
    )
    (net (code "354") (name "SG") (class "Default")
      (node (ref "DP1") (pin "7") (pinfunction "7_7") (pintype "bidirectional"))
      (node (ref "R47") (pin "2") (pinfunction "2_2") (pintype "passive"))
    )
    (net (code "355") (name "SG'") (class "Default")
      (node (ref "IC10") (pin "G") (pinfunction "G_G") (pintype "bidirectional"))
      (node (ref "PH13") (pin "2") (pinfunction "2_2") (pintype "passive"))
      (node (ref "R47") (pin "1") (pinfunction "1_1") (pintype "passive"))
    )
    (net (code "356") (name "SHDN") (class "Default")
      (node (ref "IC11") (pin "12") (pinfunction "SHND_12") (pintype "output"))
    )
    (net (code "357") (name "VCC") (class "Default")
      (node (ref "C22") (pin "1") (pinfunction "1_1") (pintype "passive"))
      (node (ref "C34") (pin "1") (pinfunction "1_1") (pintype "passive"))
      (node (ref "IC1") (pin "4") (pinfunction "VCC_4") (pintype "power_in"))
      (node (ref "IC10") (pin "BI/RBO") (pinfunction "BI/RBO_BI/RBO") (pintype "bidirectional"))
      (node (ref "IC10") (pin "LT") (pinfunction "LT_LT") (pintype "bidirectional"))
      (node (ref "IC10") (pin "VCC") (pinfunction "VCC_VCC") (pintype "bidirectional"))
      (node (ref "IC12") (pin "4") (pinfunction "VCC_4") (pintype "power_in"))
      (node (ref "IC14") (pin "1") (pinfunction "IN_1") (pintype "input"))
      (node (ref "IC14") (pin "3") (pinfunction "EN_3") (pintype "input"))
      (node (ref "IC2") (pin "4") (pinfunction "VCC_4") (pintype "power_in"))
      (node (ref "IC3") (pin "14") (pinfunction "VCC_14") (pintype "power_in"))
      (node (ref "IC4") (pin "14") (pinfunction "VCC_14") (pintype "power_in"))
      (node (ref "IC5") (pin "14") (pinfunction "VCC_14") (pintype "power_in"))
      (node (ref "IC6") (pin "16") (pinfunction "VDD_16") (pintype "power_in"))
      (node (ref "IC7") (pin "16") (pinfunction "VDD_16") (pintype "power_in"))
      (node (ref "IC8") (pin "4") (pinfunction "R_4") (pintype "input"))
      (node (ref "IC8") (pin "8") (pinfunction "V+_8") (pintype "power_in"))
      (node (ref "IC9") (pin "5") (pinfunction "VDD_5") (pintype "bidirectional"))
      (node (ref "PH58") (pin "1") (pinfunction "1_1") (pintype "passive"))
      (node (ref "PH58") (pin "10") (pinfunction "10_10") (pintype "passive"))
      (node (ref "PH58") (pin "11") (pinfunction "11_11") (pintype "passive"))
      (node (ref "PH58") (pin "12") (pinfunction "12_12") (pintype "passive"))
      (node (ref "PH58") (pin "13") (pinfunction "13_13") (pintype "passive"))
      (node (ref "PH58") (pin "14") (pinfunction "14_14") (pintype "passive"))
      (node (ref "PH58") (pin "15") (pinfunction "15_15") (pintype "passive"))
      (node (ref "PH58") (pin "16") (pinfunction "16_16") (pintype "passive"))
      (node (ref "PH58") (pin "17") (pinfunction "17_17") (pintype "passive"))
      (node (ref "PH58") (pin "18") (pinfunction "18_18") (pintype "passive"))
      (node (ref "PH58") (pin "19") (pinfunction "19_19") (pintype "passive"))
      (node (ref "PH58") (pin "2") (pinfunction "2_2") (pintype "passive"))
      (node (ref "PH58") (pin "20") (pinfunction "20_20") (pintype "passive"))
      (node (ref "PH58") (pin "21") (pinfunction "21_21") (pintype "passive"))
      (node (ref "PH58") (pin "22") (pinfunction "22_22") (pintype "passive"))
      (node (ref "PH58") (pin "23") (pinfunction "23_23") (pintype "passive"))
      (node (ref "PH58") (pin "24") (pinfunction "24_24") (pintype "passive"))
      (node (ref "PH58") (pin "25") (pinfunction "25_25") (pintype "passive"))
      (node (ref "PH58") (pin "26") (pinfunction "26_26") (pintype "passive"))
      (node (ref "PH58") (pin "27") (pinfunction "27_27") (pintype "passive"))
      (node (ref "PH58") (pin "28") (pinfunction "28_28") (pintype "passive"))
      (node (ref "PH58") (pin "29") (pinfunction "29_29") (pintype "passive"))
      (node (ref "PH58") (pin "3") (pinfunction "3_3") (pintype "passive"))
      (node (ref "PH58") (pin "30") (pinfunction "30_30") (pintype "passive"))
      (node (ref "PH58") (pin "4") (pinfunction "4_4") (pintype "passive"))
      (node (ref "PH58") (pin "5") (pinfunction "5_5") (pintype "passive"))
      (node (ref "PH58") (pin "6") (pinfunction "6_6") (pintype "passive"))
      (node (ref "PH58") (pin "7") (pinfunction "7_7") (pintype "passive"))
      (node (ref "PH58") (pin "8") (pinfunction "8_8") (pintype "passive"))
      (node (ref "PH58") (pin "9") (pinfunction "9_9") (pintype "passive"))
      (node (ref "R31") (pin "1") (pinfunction "1_1") (pintype "passive"))
      (node (ref "S1") (pin "2") (pinfunction "LC_2") (pintype "passive"))
    )
    (net (code "358") (name "VEXT") (class "Default")
      (node (ref "PH63") (pin "15") (pinfunction "15_15") (pintype "passive"))
      (node (ref "S1") (pin "1") (pinfunction "L1_1") (pintype "passive"))
    )
    (net (code "359") (name "VREF") (class "Default")
      (node (ref "C25") (pin "1") (pinfunction "1_1") (pintype "passive"))
      (node (ref "IC11") (pin "8") (pinfunction "VREF_8") (pintype "input"))
    )
    (net (code "360") (name "VUSB") (class "Default")
      (node (ref "S1") (pin "3") (pinfunction "L2_3") (pintype "passive"))
      (node (ref "U1") (pin "1") (pinfunction "VCC_1") (pintype "bidirectional"))
      (node (ref "U2") (pin "VBUS") (pinfunction "VBUS_VBUS") (pintype "bidirectional"))
    )
    (net (code "361") (name "X") (class "Default")
      (node (ref "IC12") (pin "1") (pinfunction "1OUT_1") (pintype "output"))
      (node (ref "JMP7") (pin "3") (pinfunction "3_3") (pintype "passive"))
      (node (ref "R61") (pin "1") (pinfunction "1_1") (pintype "passive"))
    )
    (net (code "362") (name "X+") (class "Default")
      (node (ref "C29") (pin "1") (pinfunction "1_1") (pintype "passive"))
      (node (ref "IC12") (pin "3") (pinfunction "1IN+_3") (pintype "input"))
      (node (ref "IC13") (pin "5") (pinfunction "XOUT_5") (pintype "bidirectional"))
      (node (ref "JMP7") (pin "1") (pinfunction "1_1") (pintype "passive"))
    )
    (net (code "363") (name "X-") (class "Default")
      (node (ref "IC12") (pin "2") (pinfunction "1IN-_2") (pintype "input"))
      (node (ref "R61") (pin "2") (pinfunction "2_2") (pintype "passive"))
      (node (ref "R64") (pin "1") (pinfunction "1_1") (pintype "passive"))
    )
    (net (code "364") (name "Y") (class "Default")
      (node (ref "IC12") (pin "7") (pinfunction "2OUT_7") (pintype "output"))
      (node (ref "JMP8") (pin "3") (pinfunction "3_3") (pintype "passive"))
      (node (ref "R62") (pin "1") (pinfunction "1_1") (pintype "passive"))
    )
    (net (code "365") (name "Y+") (class "Default")
      (node (ref "C30") (pin "1") (pinfunction "1_1") (pintype "passive"))
      (node (ref "IC12") (pin "5") (pinfunction "2IN+_5") (pintype "input"))
      (node (ref "IC13") (pin "4") (pinfunction "YOUT_4") (pintype "bidirectional"))
      (node (ref "JMP8") (pin "1") (pinfunction "1_1") (pintype "passive"))
    )
    (net (code "366") (name "Y-") (class "Default")
      (node (ref "IC12") (pin "6") (pinfunction "2IN-_6") (pintype "input"))
      (node (ref "R62") (pin "2") (pinfunction "2_2") (pintype "passive"))
      (node (ref "R65") (pin "1") (pinfunction "1_1") (pintype "passive"))
    )
    (net (code "367") (name "Z") (class "Default")
      (node (ref "IC12") (pin "8") (pinfunction "3OUT_8") (pintype "output"))
      (node (ref "JMP9") (pin "3") (pinfunction "3_3") (pintype "passive"))
      (node (ref "R63") (pin "1") (pinfunction "1_1") (pintype "passive"))
    )
    (net (code "368") (name "Z+") (class "Default")
      (node (ref "C31") (pin "1") (pinfunction "1_1") (pintype "passive"))
      (node (ref "IC12") (pin "10") (pinfunction "3IN+_10") (pintype "input"))
      (node (ref "IC13") (pin "16") (pinfunction "ZOUT_16") (pintype "bidirectional"))
      (node (ref "JMP9") (pin "1") (pinfunction "1_1") (pintype "passive"))
    )
    (net (code "369") (name "Z-") (class "Default")
      (node (ref "IC12") (pin "9") (pinfunction "3IN-_9") (pintype "input"))
      (node (ref "R63") (pin "2") (pinfunction "2_2") (pintype "passive"))
      (node (ref "R66") (pin "1") (pinfunction "1_1") (pintype "passive"))
    )
    (net (code "370") (name "unconnected-(AR3-Pad4)") (class "Default")
      (node (ref "AR3") (pin "4") (pinfunction "4_4") (pintype "bidirectional"))
    )
    (net (code "371") (name "unconnected-(AR3-Pad8)") (class "Default")
      (node (ref "AR3") (pin "8") (pinfunction "8_8") (pintype "bidirectional"))
    )
    (net (code "372") (name "unconnected-(AR4-Pad1)") (class "Default")
      (node (ref "AR4") (pin "1") (pinfunction "1_1") (pintype "bidirectional"))
    )
    (net (code "373") (name "unconnected-(AR4-Pad2)") (class "Default")
      (node (ref "AR4") (pin "2") (pinfunction "2_2") (pintype "bidirectional"))
    )
    (net (code "374") (name "unconnected-(AR4-Pad3)") (class "Default")
      (node (ref "AR4") (pin "3") (pinfunction "3_3") (pintype "bidirectional"))
    )
    (net (code "375") (name "unconnected-(AR4-Pad4)") (class "Default")
      (node (ref "AR4") (pin "4") (pinfunction "4_4") (pintype "bidirectional"))
    )
    (net (code "376") (name "unconnected-(IC11-+OUT_L-Pad1)") (class "Default")
      (node (ref "IC11") (pin "1") (pinfunction "+OUT_L_1") (pintype "input"))
    )
    (net (code "377") (name "unconnected-(IC11--OUT_L-Pad3)") (class "Default")
      (node (ref "IC11") (pin "3") (pinfunction "-OUT_L_3") (pintype "input"))
    )
    (net (code "378") (name "unconnected-(IC11-INL-Pad7)") (class "Default")
      (node (ref "IC11") (pin "7") (pinfunction "INL_7") (pintype "input"))
    )
    (net (code "379") (name "unconnected-(IC12-4IN+-Pad12)") (class "Default")
      (node (ref "IC12") (pin "12") (pinfunction "4IN+_12") (pintype "input"))
    )
    (net (code "380") (name "unconnected-(IC12-4IN--Pad13)") (class "Default")
      (node (ref "IC12") (pin "13") (pinfunction "4IN-_13") (pintype "input"))
    )
    (net (code "381") (name "unconnected-(IC12-4OUT-Pad14)") (class "Default")
      (node (ref "IC12") (pin "14") (pinfunction "4OUT_14") (pintype "output"))
    )
    (net (code "382") (name "unconnected-(IC13-ST-Pad2)") (class "Default")
      (node (ref "IC13") (pin "2") (pinfunction "ST_2") (pintype "bidirectional"))
    )
    (net (code "383") (name "unconnected-(IC14-BP-Pad4)") (class "Default")
      (node (ref "IC14") (pin "4") (pinfunction "BP_4") (pintype "input"))
    )
    (net (code "384") (name "unconnected-(JC1-Pad4)") (class "Default")
      (node (ref "JC1") (pin "4") (pinfunction "4_4") (pintype "bidirectional"))
    )
    (net (code "385") (name "unconnected-(JC1-Pad5)") (class "Default")
      (node (ref "JC1") (pin "5") (pinfunction "5_5") (pintype "bidirectional"))
    )
    (net (code "386") (name "unconnected-(S1-R1-Pad4)") (class "Default")
      (node (ref "S1") (pin "4") (pinfunction "R1_4") (pintype "passive"))
    )
    (net (code "387") (name "unconnected-(S1-R2-Pad6)") (class "Default")
      (node (ref "S1") (pin "6") (pinfunction "R2_6") (pintype "passive"))
    )
    (net (code "388") (name "unconnected-(S1-RC-Pad5)") (class "Default")
      (node (ref "S1") (pin "5") (pinfunction "RC_5") (pintype "passive"))
    )
    (net (code "389") (name "unconnected-(U1-D+-Pad3)") (class "Default")
      (node (ref "U1") (pin "3") (pinfunction "D+_3") (pintype "bidirectional"))
    )
    (net (code "390") (name "unconnected-(U1-D--Pad2)") (class "Default")
      (node (ref "U1") (pin "2") (pinfunction "D-_2") (pintype "bidirectional"))
    )
    (net (code "391") (name "unconnected-(U1-ID-Pad4)") (class "Default")
      (node (ref "U1") (pin "4") (pinfunction "ID_4") (pintype "bidirectional"))
    )
    (net (code "392") (name "unconnected-(U2-PadD+)") (class "Default")
      (node (ref "U2") (pin "D+") (pinfunction "D+_D+") (pintype "bidirectional"))
    )
    (net (code "393") (name "unconnected-(U2-PadD-)") (class "Default")
      (node (ref "U2") (pin "D-") (pinfunction "D-_D-") (pintype "bidirectional"))
    )
  )
)
